# Main.net
KiCad netlist of a schematic drawn in EAGLE
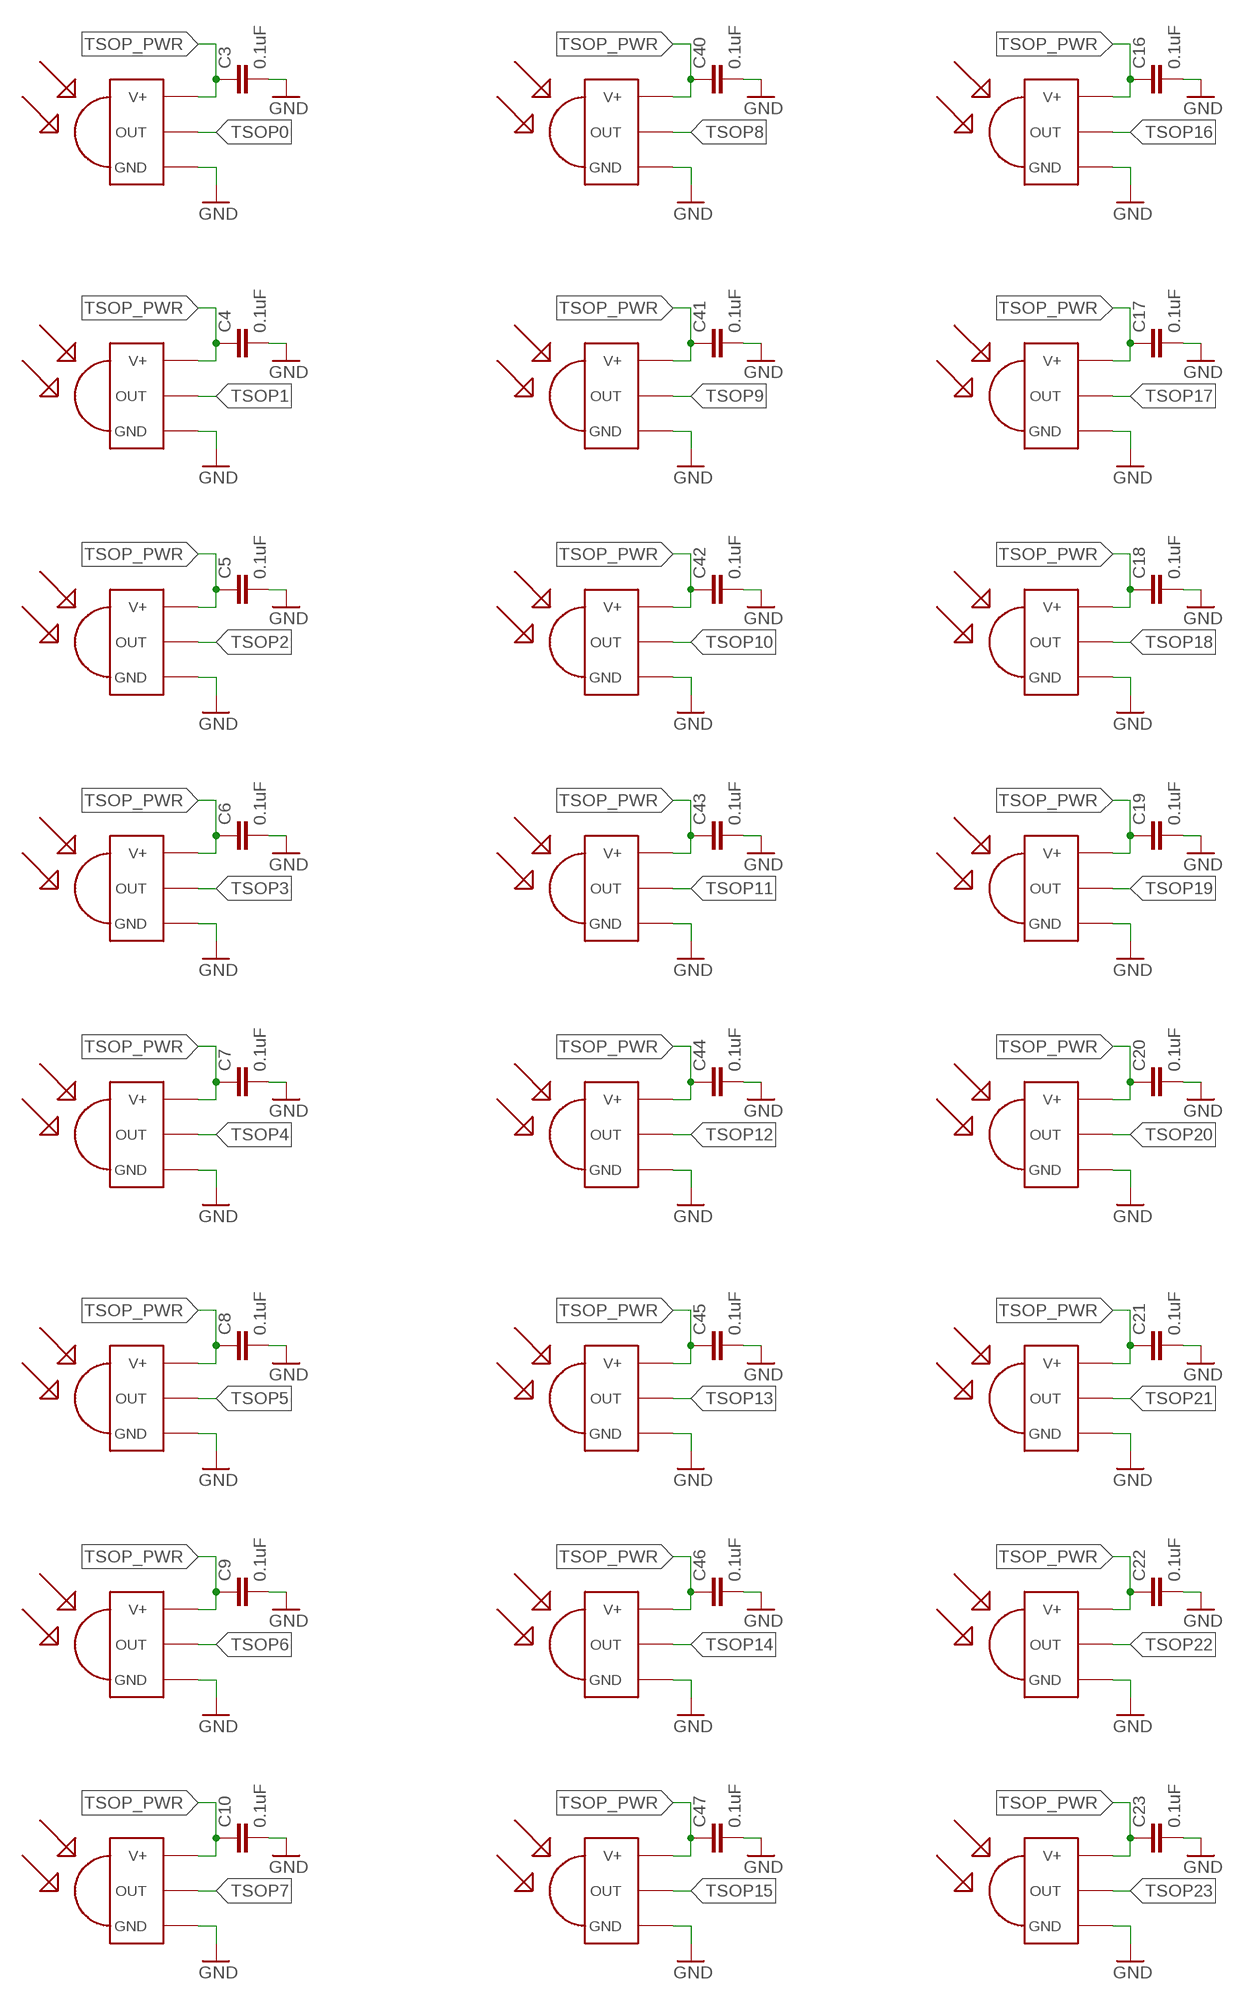
[diagram p0: schematic, sheet 1, part 1 of 3]
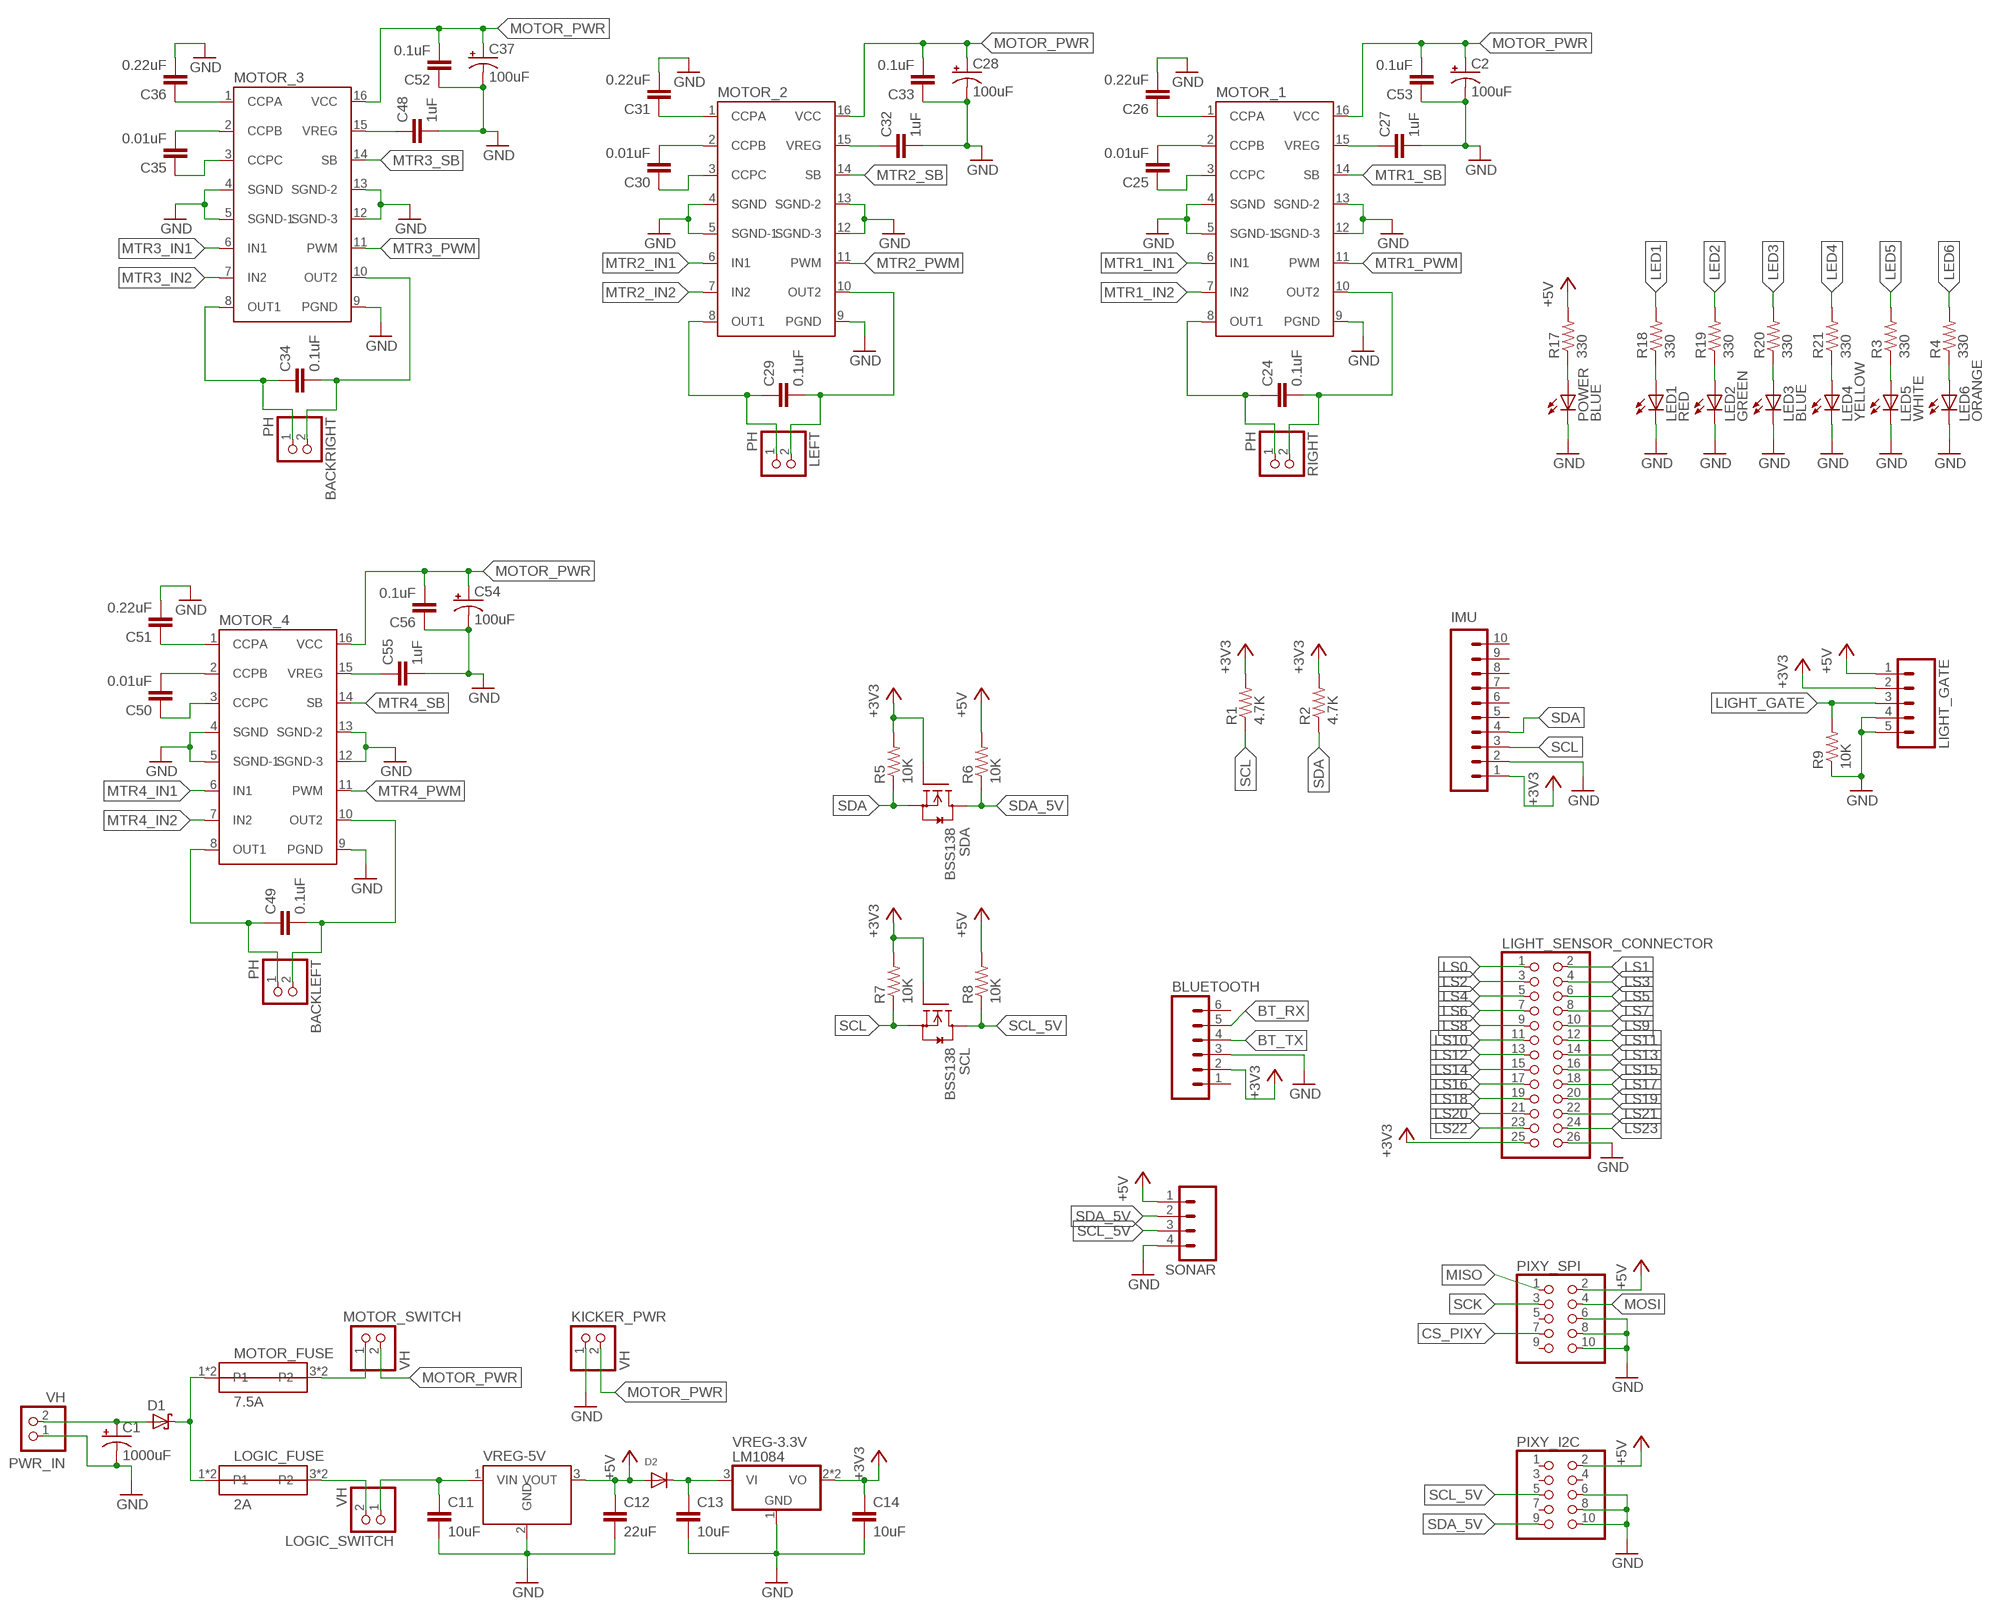
[diagram p1: schematic, sheet 1, part 2 of 3]
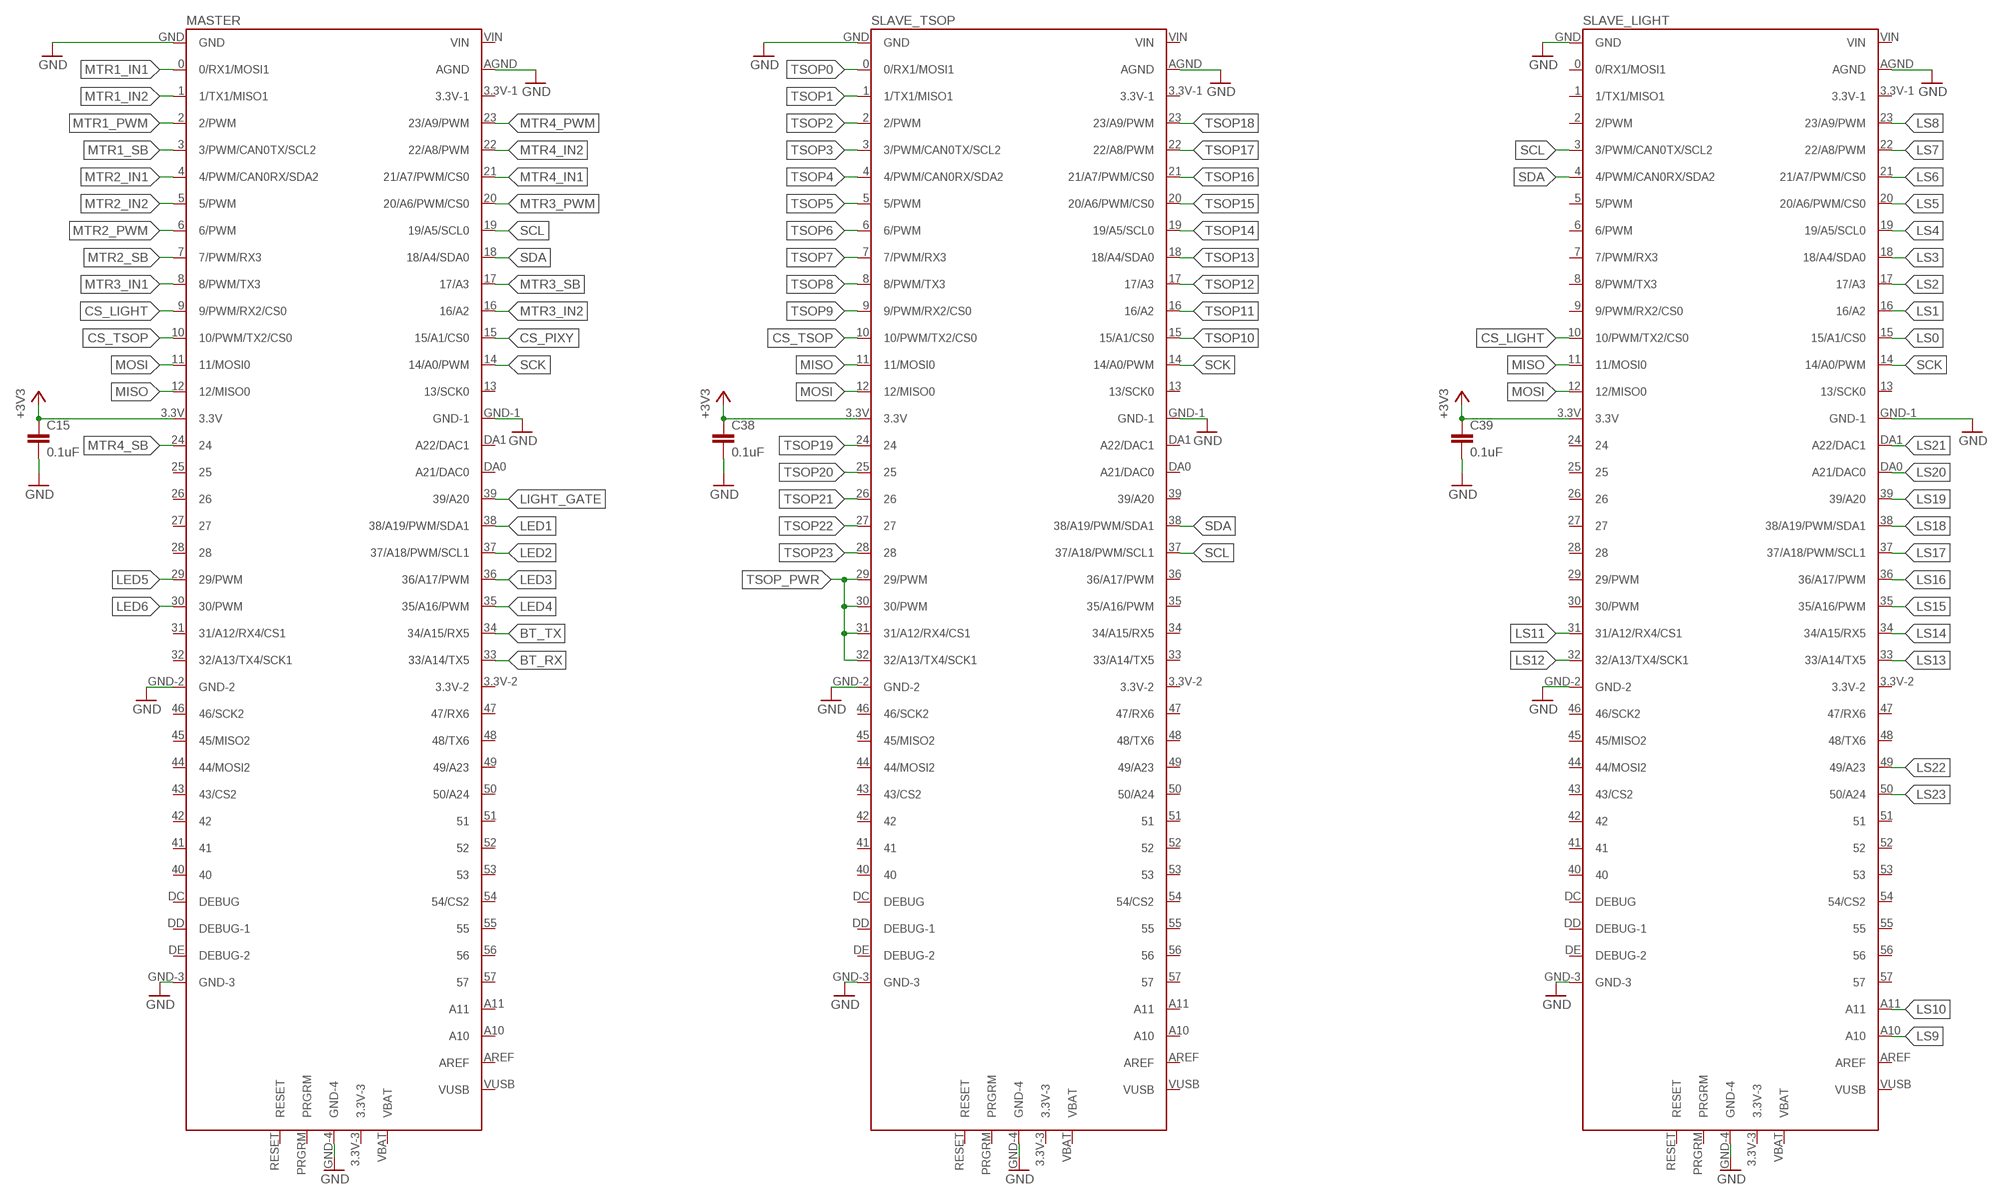
[diagram p2: schematic, sheet 1, part 3 of 3]

(export (version "E")
  (design (tool "Eeschema 10.0.6"))
  (components
    (comp (ref "0")
      (value "TSOP1737")
      (footprint "eagle-import:TSOP17XX")
      (libsource (lib "eagle-import") (part "TSOP1737"))
    )
    (comp (ref "1")
      (value "TSOP1737")
      (footprint "eagle-import:TSOP17XX")
      (libsource (lib "eagle-import") (part "TSOP1737"))
    )
    (comp (ref "2")
      (value "TSOP1737")
      (footprint "eagle-import:TSOP17XX")
      (libsource (lib "eagle-import") (part "TSOP1737"))
    )
    (comp (ref "3")
      (value "TSOP1737")
      (footprint "eagle-import:TSOP17XX")
      (libsource (lib "eagle-import") (part "TSOP1737"))
    )
    (comp (ref "4")
      (value "TSOP1737")
      (footprint "eagle-import:TSOP17XX")
      (libsource (lib "eagle-import") (part "TSOP1737"))
    )
    (comp (ref "5")
      (value "TSOP1737")
      (footprint "eagle-import:TSOP17XX")
      (libsource (lib "eagle-import") (part "TSOP1737"))
    )
    (comp (ref "6")
      (value "TSOP1737")
      (footprint "eagle-import:TSOP17XX")
      (libsource (lib "eagle-import") (part "TSOP1737"))
    )
    (comp (ref "7")
      (value "TSOP1737")
      (footprint "eagle-import:TSOP17XX")
      (libsource (lib "eagle-import") (part "TSOP1737"))
    )
    (comp (ref "8")
      (value "TSOP1737")
      (footprint "eagle-import:TSOP17XX")
      (libsource (lib "eagle-import") (part "TSOP1737"))
    )
    (comp (ref "9")
      (value "TSOP1737")
      (footprint "eagle-import:TSOP17XX")
      (libsource (lib "eagle-import") (part "TSOP1737"))
    )
    (comp (ref "10")
      (value "TSOP1737")
      (footprint "eagle-import:TSOP17XX")
      (libsource (lib "eagle-import") (part "TSOP1737"))
    )
    (comp (ref "11")
      (value "TSOP1737")
      (footprint "eagle-import:TSOP17XX")
      (libsource (lib "eagle-import") (part "TSOP1737"))
    )
    (comp (ref "12")
      (value "TSOP1737")
      (footprint "eagle-import:TSOP17XX")
      (libsource (lib "eagle-import") (part "TSOP1737"))
    )
    (comp (ref "13")
      (value "TSOP1737")
      (footprint "eagle-import:TSOP17XX")
      (libsource (lib "eagle-import") (part "TSOP1737"))
    )
    (comp (ref "14")
      (value "TSOP1737")
      (footprint "eagle-import:TSOP17XX")
      (libsource (lib "eagle-import") (part "TSOP1737"))
    )
    (comp (ref "15")
      (value "TSOP1737")
      (footprint "eagle-import:TSOP17XX")
      (libsource (lib "eagle-import") (part "TSOP1737"))
    )
    (comp (ref "16")
      (value "TSOP1737")
      (footprint "eagle-import:TSOP17XX")
      (libsource (lib "eagle-import") (part "TSOP1737"))
    )
    (comp (ref "17")
      (value "TSOP1737")
      (footprint "eagle-import:TSOP17XX")
      (libsource (lib "eagle-import") (part "TSOP1737"))
    )
    (comp (ref "18")
      (value "TSOP1737")
      (footprint "eagle-import:TSOP17XX")
      (libsource (lib "eagle-import") (part "TSOP1737"))
    )
    (comp (ref "19")
      (value "TSOP1737")
      (footprint "eagle-import:TSOP17XX")
      (libsource (lib "eagle-import") (part "TSOP1737"))
    )
    (comp (ref "20")
      (value "TSOP1737")
      (footprint "eagle-import:TSOP17XX")
      (libsource (lib "eagle-import") (part "TSOP1737"))
    )
    (comp (ref "21")
      (value "TSOP1737")
      (footprint "eagle-import:TSOP17XX")
      (libsource (lib "eagle-import") (part "TSOP1737"))
    )
    (comp (ref "22")
      (value "TSOP1737")
      (footprint "eagle-import:TSOP17XX")
      (libsource (lib "eagle-import") (part "TSOP1737"))
    )
    (comp (ref "23")
      (value "TSOP1737")
      (footprint "eagle-import:TSOP17XX")
      (libsource (lib "eagle-import") (part "TSOP1737"))
    )
    (comp (ref "BACKLEFT")
      (value "PH")
      (footprint "eagle-import:JST-PH-2-THM")
      (libsource (lib "eagle-import") (part "JST_2PIN-THM"))
    )
    (comp (ref "BACKRIGHT")
      (value "PH")
      (footprint "eagle-import:JST-PH-2-THM")
      (libsource (lib "eagle-import") (part "JST_2PIN-THM"))
    )
    (comp (ref "BLUETOOTH")
      (value "M06SILK_FEMALE_PTH")
      (footprint "eagle-import:1X06")
      (libsource (lib "eagle-import") (part "M06SILK_FEMALE_PTH"))
    )
    (comp (ref "C1")
      (value "1000uF")
      (footprint "eagle-import:CPOL-RADIAL-1000UF-25V")
      (libsource (lib "eagle-import") (part "CAP_POLPTH4"))
    )
    (comp (ref "C2")
      (value "100uF")
      (footprint "eagle-import:CPOL-RADIAL-100UF-25V")
      (libsource (lib "eagle-import") (part "CAP_POLPTH1"))
    )
    (comp (ref "C3")
      (value "0.1uF")
      (footprint "eagle-import:0603-CAP")
      (libsource (lib "eagle-import") (part "CAP0603-CAP"))
    )
    (comp (ref "C4")
      (value "0.1uF")
      (footprint "eagle-import:0603-CAP")
      (libsource (lib "eagle-import") (part "CAP0603-CAP"))
    )
    (comp (ref "C5")
      (value "0.1uF")
      (footprint "eagle-import:0603-CAP")
      (libsource (lib "eagle-import") (part "CAP0603-CAP"))
    )
    (comp (ref "C6")
      (value "0.1uF")
      (footprint "eagle-import:0603-CAP")
      (libsource (lib "eagle-import") (part "CAP0603-CAP"))
    )
    (comp (ref "C7")
      (value "0.1uF")
      (footprint "eagle-import:0603-CAP")
      (libsource (lib "eagle-import") (part "CAP0603-CAP"))
    )
    (comp (ref "C8")
      (value "0.1uF")
      (footprint "eagle-import:0603-CAP")
      (libsource (lib "eagle-import") (part "CAP0603-CAP"))
    )
    (comp (ref "C9")
      (value "0.1uF")
      (footprint "eagle-import:0603-CAP")
      (libsource (lib "eagle-import") (part "CAP0603-CAP"))
    )
    (comp (ref "C10")
      (value "0.1uF")
      (footprint "eagle-import:0603-CAP")
      (libsource (lib "eagle-import") (part "CAP0603-CAP"))
    )
    (comp (ref "C11")
      (value "10uF")
      (footprint "eagle-import:0805")
      (libsource (lib "eagle-import") (part "CAP0805"))
    )
    (comp (ref "C12")
      (value "22uF")
      (footprint "eagle-import:0805")
      (libsource (lib "eagle-import") (part "CAP0805"))
    )
    (comp (ref "C13")
      (value "10uF")
      (footprint "eagle-import:0805")
      (libsource (lib "eagle-import") (part "CAP0805"))
    )
    (comp (ref "C14")
      (value "10uF")
      (footprint "eagle-import:0805")
      (libsource (lib "eagle-import") (part "CAP0805"))
    )
    (comp (ref "C15")
      (value "0.1uF")
      (footprint "eagle-import:0603-CAP")
      (libsource (lib "eagle-import") (part "CAP0603-CAP"))
    )
    (comp (ref "C16")
      (value "0.1uF")
      (footprint "eagle-import:0603-CAP")
      (libsource (lib "eagle-import") (part "CAP0603-CAP"))
    )
    (comp (ref "C17")
      (value "0.1uF")
      (footprint "eagle-import:0603-CAP")
      (libsource (lib "eagle-import") (part "CAP0603-CAP"))
    )
    (comp (ref "C18")
      (value "0.1uF")
      (footprint "eagle-import:0603-CAP")
      (libsource (lib "eagle-import") (part "CAP0603-CAP"))
    )
    (comp (ref "C19")
      (value "0.1uF")
      (footprint "eagle-import:0603-CAP")
      (libsource (lib "eagle-import") (part "CAP0603-CAP"))
    )
    (comp (ref "C20")
      (value "0.1uF")
      (footprint "eagle-import:0603-CAP")
      (libsource (lib "eagle-import") (part "CAP0603-CAP"))
    )
    (comp (ref "C21")
      (value "0.1uF")
      (footprint "eagle-import:0603-CAP")
      (libsource (lib "eagle-import") (part "CAP0603-CAP"))
    )
    (comp (ref "C22")
      (value "0.1uF")
      (footprint "eagle-import:0603-CAP")
      (libsource (lib "eagle-import") (part "CAP0603-CAP"))
    )
    (comp (ref "C23")
      (value "0.1uF")
      (footprint "eagle-import:0603-CAP")
      (libsource (lib "eagle-import") (part "CAP0603-CAP"))
    )
    (comp (ref "C24")
      (value "0.1uF")
      (footprint "eagle-import:0603-CAP")
      (libsource (lib "eagle-import") (part "CAP0603-CAP"))
    )
    (comp (ref "C25")
      (value "0.01uF")
      (footprint "eagle-import:0603-CAP")
      (libsource (lib "eagle-import") (part "CAP0603-CAP"))
    )
    (comp (ref "C26")
      (value "0.22uF")
      (footprint "eagle-import:0603-CAP")
      (libsource (lib "eagle-import") (part "CAP0603-CAP"))
    )
    (comp (ref "C27")
      (value "1uF")
      (footprint "eagle-import:0603-CAP")
      (libsource (lib "eagle-import") (part "CAP0603-CAP"))
    )
    (comp (ref "C28")
      (value "100uF")
      (footprint "eagle-import:CPOL-RADIAL-100UF-25V")
      (libsource (lib "eagle-import") (part "CAP_POLPTH1"))
    )
    (comp (ref "C29")
      (value "0.1uF")
      (footprint "eagle-import:0603-CAP")
      (libsource (lib "eagle-import") (part "CAP0603-CAP"))
    )
    (comp (ref "C30")
      (value "0.01uF")
      (footprint "eagle-import:0603-CAP")
      (libsource (lib "eagle-import") (part "CAP0603-CAP"))
    )
    (comp (ref "C31")
      (value "0.22uF")
      (footprint "eagle-import:0603-CAP")
      (libsource (lib "eagle-import") (part "CAP0603-CAP"))
    )
    (comp (ref "C32")
      (value "1uF")
      (footprint "eagle-import:0603-CAP")
      (libsource (lib "eagle-import") (part "CAP0603-CAP"))
    )
    (comp (ref "C33")
      (value "0.1uF")
      (footprint "eagle-import:0603-CAP")
      (libsource (lib "eagle-import") (part "CAP0603-CAP"))
    )
    (comp (ref "C34")
      (value "0.1uF")
      (footprint "eagle-import:0603-CAP")
      (libsource (lib "eagle-import") (part "CAP0603-CAP"))
    )
    (comp (ref "C35")
      (value "0.01uF")
      (footprint "eagle-import:0603-CAP")
      (libsource (lib "eagle-import") (part "CAP0603-CAP"))
    )
    (comp (ref "C36")
      (value "0.22uF")
      (footprint "eagle-import:0603-CAP")
      (libsource (lib "eagle-import") (part "CAP0603-CAP"))
    )
    (comp (ref "C37")
      (value "100uF")
      (footprint "eagle-import:CPOL-RADIAL-100UF-25V")
      (libsource (lib "eagle-import") (part "CAP_POLPTH1"))
    )
    (comp (ref "C38")
      (value "0.1uF")
      (footprint "eagle-import:0603-CAP")
      (libsource (lib "eagle-import") (part "CAP0603-CAP"))
    )
    (comp (ref "C39")
      (value "0.1uF")
      (footprint "eagle-import:0603-CAP")
      (libsource (lib "eagle-import") (part "CAP0603-CAP"))
    )
    (comp (ref "C40")
      (value "0.1uF")
      (footprint "eagle-import:0603-CAP")
      (libsource (lib "eagle-import") (part "CAP0603-CAP"))
    )
    (comp (ref "C41")
      (value "0.1uF")
      (footprint "eagle-import:0603-CAP")
      (libsource (lib "eagle-import") (part "CAP0603-CAP"))
    )
    (comp (ref "C42")
      (value "0.1uF")
      (footprint "eagle-import:0603-CAP")
      (libsource (lib "eagle-import") (part "CAP0603-CAP"))
    )
    (comp (ref "C43")
      (value "0.1uF")
      (footprint "eagle-import:0603-CAP")
      (libsource (lib "eagle-import") (part "CAP0603-CAP"))
    )
    (comp (ref "C44")
      (value "0.1uF")
      (footprint "eagle-import:0603-CAP")
      (libsource (lib "eagle-import") (part "CAP0603-CAP"))
    )
    (comp (ref "C45")
      (value "0.1uF")
      (footprint "eagle-import:0603-CAP")
      (libsource (lib "eagle-import") (part "CAP0603-CAP"))
    )
    (comp (ref "C46")
      (value "0.1uF")
      (footprint "eagle-import:0603-CAP")
      (libsource (lib "eagle-import") (part "CAP0603-CAP"))
    )
    (comp (ref "C47")
      (value "0.1uF")
      (footprint "eagle-import:0603-CAP")
      (libsource (lib "eagle-import") (part "CAP0603-CAP"))
    )
    (comp (ref "C48")
      (value "1uF")
      (footprint "eagle-import:0603-CAP")
      (libsource (lib "eagle-import") (part "CAP0603-CAP"))
    )
    (comp (ref "C49")
      (value "0.1uF")
      (footprint "eagle-import:0603-CAP")
      (libsource (lib "eagle-import") (part "CAP0603-CAP"))
    )
    (comp (ref "C50")
      (value "0.01uF")
      (footprint "eagle-import:0603-CAP")
      (libsource (lib "eagle-import") (part "CAP0603-CAP"))
    )
    (comp (ref "C51")
      (value "0.22uF")
      (footprint "eagle-import:0603-CAP")
      (libsource (lib "eagle-import") (part "CAP0603-CAP"))
    )
    (comp (ref "C52")
      (value "0.1uF")
      (footprint "eagle-import:0603-CAP")
      (libsource (lib "eagle-import") (part "CAP0603-CAP"))
    )
    (comp (ref "C53")
      (value "0.1uF")
      (footprint "eagle-import:0603-CAP")
      (libsource (lib "eagle-import") (part "CAP0603-CAP"))
    )
    (comp (ref "C54")
      (value "100uF")
      (footprint "eagle-import:CPOL-RADIAL-100UF-25V")
      (libsource (lib "eagle-import") (part "CAP_POLPTH1"))
    )
    (comp (ref "C55")
      (value "1uF")
      (footprint "eagle-import:0603-CAP")
      (libsource (lib "eagle-import") (part "CAP0603-CAP"))
    )
    (comp (ref "C56")
      (value "0.1uF")
      (footprint "eagle-import:0603-CAP")
      (libsource (lib "eagle-import") (part "CAP0603-CAP"))
    )
    (comp (ref "D1")
      (value "SCHOTTKY-DIODEP6T15")
      (footprint "eagle-import:P6T15")
      (libsource (lib "eagle-import") (part "SCHOTTKY-DIODEP6T15"))
    )
    (comp (ref "D2")
      (value "DIODE_SOD-123FL")
      (footprint "eagle-import:SOD-123FL")
      (libsource (lib "eagle-import") (part "DIODE_SOD-123FL"))
    )
    (comp (ref "IMU")
      (value "M10SILK_FEMALE_PTH")
      (footprint "eagle-import:1X10")
      (libsource (lib "eagle-import") (part "M10SILK_FEMALE_PTH"))
    )
    (comp (ref "KICKER_PWR")
      (value "VH")
      (footprint "eagle-import:B2P-VH")
      (libsource (lib "eagle-import") (part "B2P-VH"))
    )
    (comp (ref "LED1")
      (value "RED")
      (footprint "eagle-import:CHIPLED_0603")
      (libsource (lib "eagle-import") (part "LEDCHIPLED_0603"))
    )
    (comp (ref "LED2")
      (value "GREEN")
      (footprint "eagle-import:CHIPLED_0603")
      (libsource (lib "eagle-import") (part "LEDCHIPLED_0603"))
    )
    (comp (ref "LED3")
      (value "BLUE")
      (footprint "eagle-import:CHIPLED_0603")
      (libsource (lib "eagle-import") (part "LEDCHIPLED_0603"))
    )
    (comp (ref "LED4")
      (value "YELLOW")
      (footprint "eagle-import:CHIPLED_0603")
      (libsource (lib "eagle-import") (part "LEDCHIPLED_0603"))
    )
    (comp (ref "LED5")
      (value "WHITE")
      (footprint "eagle-import:CHIPLED_0603")
      (libsource (lib "eagle-import") (part "LEDCHIPLED_0603"))
    )
    (comp (ref "LED6")
      (value "ORANGE")
      (footprint "eagle-import:CHIPLED_0603")
      (libsource (lib "eagle-import") (part "LEDCHIPLED_0603"))
    )
    (comp (ref "LEFT")
      (value "PH")
      (footprint "eagle-import:JST-PH-2-THM")
      (libsource (lib "eagle-import") (part "JST_2PIN-THM"))
    )
    (comp (ref "LIGHT_GATE")
      (value "M05PTH")
      (footprint "eagle-import:1X05")
      (libsource (lib "eagle-import") (part "M05PTH"))
    )
    (comp (ref "LIGHT_SENSOR_CONNECTOR")
      (value "PINHD-2X13SMT")
      (footprint "eagle-import:2X13_SMT")
      (libsource (lib "eagle-import") (part "PINHD-2X13SMT"))
    )
    (comp (ref "LOGIC_FUSE")
      (value "2A")
      (footprint "eagle-import:3568-FUSEHOLDER")
      (libsource (lib "eagle-import") (part "3568-FUSEHOLDER"))
    )
    (comp (ref "LOGIC_SWITCH")
      (value "VH")
      (footprint "eagle-import:B2P-VH")
      (libsource (lib "eagle-import") (part "B2P-VH"))
    )
    (comp (ref "MASTER")
      (value "TEENSY-3.5")
      (footprint "eagle-import:TEENSY-3.5")
      (libsource (lib "eagle-import") (part "TEENSY-3.5"))
    )
    (comp (ref "MOTOR_1")
      (value "TB6549PG")
      (footprint "eagle-import:TB6549PG")
      (libsource (lib "eagle-import") (part "TB6549PG"))
    )
    (comp (ref "MOTOR_2")
      (value "TB6549PG")
      (footprint "eagle-import:TB6549PG")
      (libsource (lib "eagle-import") (part "TB6549PG"))
    )
    (comp (ref "MOTOR_3")
      (value "TB6549PG")
      (footprint "eagle-import:TB6549PG")
      (libsource (lib "eagle-import") (part "TB6549PG"))
    )
    (comp (ref "MOTOR_4")
      (value "TB6549PG")
      (footprint "eagle-import:TB6549PG")
      (libsource (lib "eagle-import") (part "TB6549PG"))
    )
    (comp (ref "MOTOR_FUSE")
      (value "7.5A")
      (footprint "eagle-import:3568-FUSEHOLDER")
      (libsource (lib "eagle-import") (part "3568-FUSEHOLDER"))
    )
    (comp (ref "MOTOR_SWITCH")
      (value "VH")
      (footprint "eagle-import:B2P-VH")
      (libsource (lib "eagle-import") (part "B2P-VH"))
    )
    (comp (ref "PIXY_I2C")
      (value "PINHD-2X5SMT")
      (footprint "eagle-import:2X05_SMT")
      (libsource (lib "eagle-import") (part "PINHD-2X5SMT"))
    )
    (comp (ref "PIXY_SPI")
      (value "PINHD-2X5SMT")
      (footprint "eagle-import:2X05_SMT")
      (libsource (lib "eagle-import") (part "PINHD-2X5SMT"))
    )
    (comp (ref "POWER")
      (value "BLUE")
      (footprint "eagle-import:CHIPLED_0603")
      (libsource (lib "eagle-import") (part "LEDCHIPLED_0603"))
    )
    (comp (ref "PWR_IN")
      (value "VH")
      (footprint "eagle-import:B2P-VH")
      (libsource (lib "eagle-import") (part "B2P-VH"))
    )
    (comp (ref "R1")
      (value "4.7K")
      (footprint "eagle-import:0603-RES")
      (libsource (lib "eagle-import") (part "RESISTOR0603"))
    )
    (comp (ref "R2")
      (value "4.7K")
      (footprint "eagle-import:0603-RES")
      (libsource (lib "eagle-import") (part "RESISTOR0603"))
    )
    (comp (ref "R3")
      (value "330")
      (footprint "eagle-import:0603-RES")
      (libsource (lib "eagle-import") (part "RESISTOR0603"))
    )
    (comp (ref "R4")
      (value "330")
      (footprint "eagle-import:0603-RES")
      (libsource (lib "eagle-import") (part "RESISTOR0603"))
    )
    (comp (ref "R5")
      (value "10K")
      (footprint "eagle-import:0603-RES")
      (libsource (lib "eagle-import") (part "RESISTOR0603-RES"))
    )
    (comp (ref "R6")
      (value "10K")
      (footprint "eagle-import:0603-RES")
      (libsource (lib "eagle-import") (part "RESISTOR0603-RES"))
    )
    (comp (ref "R7")
      (value "10K")
      (footprint "eagle-import:0603-RES")
      (libsource (lib "eagle-import") (part "RESISTOR0603-RES"))
    )
    (comp (ref "R8")
      (value "10K")
      (footprint "eagle-import:0603-RES")
      (libsource (lib "eagle-import") (part "RESISTOR0603-RES"))
    )
    (comp (ref "R9")
      (value "10K")
      (footprint "eagle-import:0603-RES")
      (libsource (lib "eagle-import") (part "RESISTOR0603-RES"))
    )
    (comp (ref "R17")
      (value "330")
      (footprint "eagle-import:0603-RES")
      (libsource (lib "eagle-import") (part "RESISTOR0603"))
    )
    (comp (ref "R18")
      (value "330")
      (footprint "eagle-import:0603-RES")
      (libsource (lib "eagle-import") (part "RESISTOR0603"))
    )
    (comp (ref "R19")
      (value "330")
      (footprint "eagle-import:0603-RES")
      (libsource (lib "eagle-import") (part "RESISTOR0603"))
    )
    (comp (ref "R20")
      (value "330")
      (footprint "eagle-import:0603-RES")
      (libsource (lib "eagle-import") (part "RESISTOR0603"))
    )
    (comp (ref "R21")
      (value "330")
      (footprint "eagle-import:0603-RES")
      (libsource (lib "eagle-import") (part "RESISTOR0603"))
    )
    (comp (ref "RIGHT")
      (value "PH")
      (footprint "eagle-import:JST-PH-2-THM")
      (libsource (lib "eagle-import") (part "JST_2PIN-THM"))
    )
    (comp (ref "SCL")
      (value "BSS138")
      (footprint "eagle-import:SOT23")
      (libsource (lib "eagle-import") (part "BSS138"))
    )
    (comp (ref "SDA")
      (value "BSS138")
      (footprint "eagle-import:SOT23")
      (libsource (lib "eagle-import") (part "BSS138"))
    )
    (comp (ref "SLAVE_LIGHT")
      (value "TEENSY-3.5")
      (footprint "eagle-import:TEENSY-3.5")
      (libsource (lib "eagle-import") (part "TEENSY-3.5"))
    )
    (comp (ref "SLAVE_TSOP")
      (value "TEENSY-3.5")
      (footprint "eagle-import:TEENSY-3.5")
      (libsource (lib "eagle-import") (part "TEENSY-3.5"))
    )
    (comp (ref "SONAR")
      (value "M04PTH")
      (footprint "eagle-import:1X04")
      (libsource (lib "eagle-import") (part "M04PTH"))
    )
    (comp (ref "VREG-3.3V")
      (value "LM1084")
      (footprint "eagle-import:TO263-3")
      (libsource (lib "eagle-import") (part "LM340?-S05"))
    )
    (comp (ref "VREG-5V")
      (value "V78-2000")
      (footprint "eagle-import:V78-2000")
      (libsource (lib "eagle-import") (part "V78-2000"))
    )
  )
  (nets
    (net (code "1") (name "+3V3") (class "Default")
      (node (ref "BLUETOOTH") (pin "2") (pinfunction "2_2") (pintype "passive"))
      (node (ref "C14") (pin "1") (pinfunction "1_1") (pintype "passive"))
      (node (ref "C15") (pin "1") (pinfunction "1_1") (pintype "passive"))
      (node (ref "C38") (pin "1") (pinfunction "1_1") (pintype "passive"))
      (node (ref "C39") (pin "1") (pinfunction "1_1") (pintype "passive"))
      (node (ref "IMU") (pin "1") (pinfunction "1_1") (pintype "passive"))
      (node (ref "LIGHT_GATE") (pin "2") (pinfunction "2_2") (pintype "passive"))
      (node (ref "LIGHT_SENSOR_CONNECTOR") (pin "25") (pinfunction "25_25") (pintype "passive"))
      (node (ref "MASTER") (pin "3.3V") (pinfunction "3.3V_3.3V") (pintype "bidirectional"))
      (node (ref "R1") (pin "2") (pinfunction "2_2") (pintype "passive"))
      (node (ref "R2") (pin "2") (pinfunction "2_2") (pintype "passive"))
      (node (ref "R5") (pin "2") (pinfunction "2_2") (pintype "passive"))
      (node (ref "R7") (pin "2") (pinfunction "2_2") (pintype "passive"))
      (node (ref "SCL") (pin "1") (pinfunction "G_1") (pintype "passive"))
      (node (ref "SDA") (pin "1") (pinfunction "G_1") (pintype "passive"))
      (node (ref "SLAVE_LIGHT") (pin "3.3V") (pinfunction "3.3V_3.3V") (pintype "bidirectional"))
      (node (ref "SLAVE_TSOP") (pin "3.3V") (pinfunction "3.3V_3.3V") (pintype "bidirectional"))
      (node (ref "VREG-3.3V") (pin "2") (pinfunction "VO_2") (pintype "passive"))
      (node (ref "VREG-3.3V") (pin "TAB") (pinfunction "VO_TAB") (pintype "passive"))
    )
    (net (code "2") (name "+5V") (class "Default")
      (node (ref "C12") (pin "1") (pinfunction "1_1") (pintype "passive"))
      (node (ref "D2") (pin "A") (pinfunction "A_A") (pintype "passive"))
      (node (ref "LIGHT_GATE") (pin "1") (pinfunction "1_1") (pintype "passive"))
      (node (ref "PIXY_I2C") (pin "2") (pinfunction "2_2") (pintype "passive"))
      (node (ref "PIXY_SPI") (pin "2") (pinfunction "2_2") (pintype "passive"))
      (node (ref "R17") (pin "2") (pinfunction "2_2") (pintype "passive"))
      (node (ref "R6") (pin "2") (pinfunction "2_2") (pintype "passive"))
      (node (ref "R8") (pin "2") (pinfunction "2_2") (pintype "passive"))
      (node (ref "SONAR") (pin "1") (pinfunction "1_1") (pintype "passive"))
      (node (ref "VREG-5V") (pin "3") (pinfunction "VOUT_3") (pintype "bidirectional"))
    )
    (net (code "3") (name "BT_RX") (class "Default")
      (node (ref "BLUETOOTH") (pin "5") (pinfunction "5_5") (pintype "passive"))
      (node (ref "MASTER") (pin "33") (pinfunction "33/A14/TX5_33") (pintype "bidirectional"))
    )
    (net (code "4") (name "BT_TX") (class "Default")
      (node (ref "BLUETOOTH") (pin "4") (pinfunction "4_4") (pintype "passive"))
      (node (ref "MASTER") (pin "34") (pinfunction "34/A15/RX5_34") (pintype "bidirectional"))
    )
    (net (code "5") (name "CS_LIGHT") (class "Default")
      (node (ref "MASTER") (pin "9") (pinfunction "9/PWM/RX2/CS0_9") (pintype "bidirectional"))
      (node (ref "SLAVE_LIGHT") (pin "10") (pinfunction "10/PWM/TX2/CS0_10") (pintype "bidirectional"))
    )
    (net (code "6") (name "CS_PIXY") (class "Default")
      (node (ref "MASTER") (pin "15") (pinfunction "15/A1/CS0_15") (pintype "bidirectional"))
      (node (ref "PIXY_SPI") (pin "7") (pinfunction "7_7") (pintype "passive"))
    )
    (net (code "7") (name "CS_TSOP") (class "Default")
      (node (ref "MASTER") (pin "10") (pinfunction "10/PWM/TX2/CS0_10") (pintype "bidirectional"))
      (node (ref "SLAVE_TSOP") (pin "10") (pinfunction "10/PWM/TX2/CS0_10") (pintype "bidirectional"))
    )
    (net (code "8") (name "GND") (class "Default")
      (node (ref "0") (pin "GND") (pinfunction "GND_GND") (pintype "bidirectional"))
      (node (ref "1") (pin "GND") (pinfunction "GND_GND") (pintype "bidirectional"))
      (node (ref "10") (pin "GND") (pinfunction "GND_GND") (pintype "bidirectional"))
      (node (ref "11") (pin "GND") (pinfunction "GND_GND") (pintype "bidirectional"))
      (node (ref "12") (pin "GND") (pinfunction "GND_GND") (pintype "bidirectional"))
      (node (ref "13") (pin "GND") (pinfunction "GND_GND") (pintype "bidirectional"))
      (node (ref "14") (pin "GND") (pinfunction "GND_GND") (pintype "bidirectional"))
      (node (ref "15") (pin "GND") (pinfunction "GND_GND") (pintype "bidirectional"))
      (node (ref "16") (pin "GND") (pinfunction "GND_GND") (pintype "bidirectional"))
      (node (ref "17") (pin "GND") (pinfunction "GND_GND") (pintype "bidirectional"))
      (node (ref "18") (pin "GND") (pinfunction "GND_GND") (pintype "bidirectional"))
      (node (ref "19") (pin "GND") (pinfunction "GND_GND") (pintype "bidirectional"))
      (node (ref "2") (pin "GND") (pinfunction "GND_GND") (pintype "bidirectional"))
      (node (ref "20") (pin "GND") (pinfunction "GND_GND") (pintype "bidirectional"))
      (node (ref "21") (pin "GND") (pinfunction "GND_GND") (pintype "bidirectional"))
      (node (ref "22") (pin "GND") (pinfunction "GND_GND") (pintype "bidirectional"))
      (node (ref "23") (pin "GND") (pinfunction "GND_GND") (pintype "bidirectional"))
      (node (ref "3") (pin "GND") (pinfunction "GND_GND") (pintype "bidirectional"))
      (node (ref "4") (pin "GND") (pinfunction "GND_GND") (pintype "bidirectional"))
      (node (ref "5") (pin "GND") (pinfunction "GND_GND") (pintype "bidirectional"))
      (node (ref "6") (pin "GND") (pinfunction "GND_GND") (pintype "bidirectional"))
      (node (ref "7") (pin "GND") (pinfunction "GND_GND") (pintype "bidirectional"))
      (node (ref "8") (pin "GND") (pinfunction "GND_GND") (pintype "bidirectional"))
      (node (ref "9") (pin "GND") (pinfunction "GND_GND") (pintype "bidirectional"))
      (node (ref "BLUETOOTH") (pin "3") (pinfunction "3_3") (pintype "passive"))
      (node (ref "C1") (pin "-") (pinfunction "-_-") (pintype "passive"))
      (node (ref "C10") (pin "2") (pinfunction "2_2") (pintype "passive"))
      (node (ref "C11") (pin "2") (pinfunction "2_2") (pintype "passive"))
      (node (ref "C12") (pin "2") (pinfunction "2_2") (pintype "passive"))
      (node (ref "C13") (pin "2") (pinfunction "2_2") (pintype "passive"))
      (node (ref "C14") (pin "2") (pinfunction "2_2") (pintype "passive"))
      (node (ref "C15") (pin "2") (pinfunction "2_2") (pintype "passive"))
      (node (ref "C16") (pin "2") (pinfunction "2_2") (pintype "passive"))
      (node (ref "C17") (pin "2") (pinfunction "2_2") (pintype "passive"))
      (node (ref "C18") (pin "2") (pinfunction "2_2") (pintype "passive"))
      (node (ref "C19") (pin "2") (pinfunction "2_2") (pintype "passive"))
      (node (ref "C2") (pin "2") (pinfunction "-_2") (pintype "passive"))
      (node (ref "C20") (pin "2") (pinfunction "2_2") (pintype "passive"))
      (node (ref "C21") (pin "2") (pinfunction "2_2") (pintype "passive"))
      (node (ref "C22") (pin "2") (pinfunction "2_2") (pintype "passive"))
      (node (ref "C23") (pin "2") (pinfunction "2_2") (pintype "passive"))
      (node (ref "C26") (pin "2") (pinfunction "2_2") (pintype "passive"))
      (node (ref "C27") (pin "2") (pinfunction "2_2") (pintype "passive"))
      (node (ref "C28") (pin "2") (pinfunction "-_2") (pintype "passive"))
      (node (ref "C3") (pin "2") (pinfunction "2_2") (pintype "passive"))
      (node (ref "C31") (pin "2") (pinfunction "2_2") (pintype "passive"))
      (node (ref "C32") (pin "2") (pinfunction "2_2") (pintype "passive"))
      (node (ref "C33") (pin "1") (pinfunction "1_1") (pintype "passive"))
      (node (ref "C36") (pin "2") (pinfunction "2_2") (pintype "passive"))
      (node (ref "C37") (pin "2") (pinfunction "-_2") (pintype "passive"))
      (node (ref "C38") (pin "2") (pinfunction "2_2") (pintype "passive"))
      (node (ref "C39") (pin "2") (pinfunction "2_2") (pintype "passive"))
      (node (ref "C4") (pin "2") (pinfunction "2_2") (pintype "passive"))
      (node (ref "C40") (pin "2") (pinfunction "2_2") (pintype "passive"))
      (node (ref "C41") (pin "2") (pinfunction "2_2") (pintype "passive"))
      (node (ref "C42") (pin "2") (pinfunction "2_2") (pintype "passive"))
      (node (ref "C43") (pin "2") (pinfunction "2_2") (pintype "passive"))
      (node (ref "C44") (pin "2") (pinfunction "2_2") (pintype "passive"))
      (node (ref "C45") (pin "2") (pinfunction "2_2") (pintype "passive"))
      (node (ref "C46") (pin "2") (pinfunction "2_2") (pintype "passive"))
      (node (ref "C47") (pin "2") (pinfunction "2_2") (pintype "passive"))
      (node (ref "C48") (pin "2") (pinfunction "2_2") (pintype "passive"))
      (node (ref "C5") (pin "2") (pinfunction "2_2") (pintype "passive"))
      (node (ref "C51") (pin "2") (pinfunction "2_2") (pintype "passive"))
      (node (ref "C52") (pin "1") (pinfunction "1_1") (pintype "passive"))
      (node (ref "C53") (pin "1") (pinfunction "1_1") (pintype "passive"))
      (node (ref "C54") (pin "2") (pinfunction "-_2") (pintype "passive"))
      (node (ref "C55") (pin "2") (pinfunction "2_2") (pintype "passive"))
      (node (ref "C56") (pin "1") (pinfunction "1_1") (pintype "passive"))
      (node (ref "C6") (pin "2") (pinfunction "2_2") (pintype "passive"))
      (node (ref "C7") (pin "2") (pinfunction "2_2") (pintype "passive"))
      (node (ref "C8") (pin "2") (pinfunction "2_2") (pintype "passive"))
      (node (ref "C9") (pin "2") (pinfunction "2_2") (pintype "passive"))
      (node (ref "IMU") (pin "2") (pinfunction "2_2") (pintype "passive"))
      (node (ref "KICKER_PWR") (pin "1") (pinfunction "1_1") (pintype "passive"))
      (node (ref "LED1") (pin "C") (pinfunction "C_C") (pintype "passive"))
      (node (ref "LED2") (pin "C") (pinfunction "C_C") (pintype "passive"))
      (node (ref "LED3") (pin "C") (pinfunction "C_C") (pintype "passive"))
      (node (ref "LED4") (pin "C") (pinfunction "C_C") (pintype "passive"))
      (node (ref "LED5") (pin "C") (pinfunction "C_C") (pintype "passive"))
      (node (ref "LED6") (pin "C") (pinfunction "C_C") (pintype "passive"))
      (node (ref "LIGHT_GATE") (pin "4") (pinfunction "4_4") (pintype "passive"))
      (node (ref "LIGHT_GATE") (pin "5") (pinfunction "5_5") (pintype "passive"))
      (node (ref "LIGHT_SENSOR_CONNECTOR") (pin "26") (pinfunction "26_26") (pintype "passive"))
      (node (ref "MASTER") (pin "AGND") (pinfunction "AGND_AGND") (pintype "bidirectional"))
      (node (ref "MASTER") (pin "GND") (pinfunction "GND_GND") (pintype "bidirectional"))
      (node (ref "MASTER") (pin "GND-1") (pinfunction "GND-1_GND-1") (pintype "bidirectional"))
      (node (ref "MASTER") (pin "GND-2") (pinfunction "GND-2_GND-2") (pintype "bidirectional"))
      (node (ref "MASTER") (pin "GND-3") (pinfunction "GND-3_GND-3") (pintype "bidirectional"))
      (node (ref "MASTER") (pin "GND-4") (pinfunction "GND-4_GND-4") (pintype "bidirectional"))
      (node (ref "MOTOR_1") (pin "12") (pinfunction "SGND-3_12") (pintype "bidirectional"))
      (node (ref "MOTOR_1") (pin "13") (pinfunction "SGND-2_13") (pintype "bidirectional"))
      (node (ref "MOTOR_1") (pin "4") (pinfunction "SGND_4") (pintype "bidirectional"))
      (node (ref "MOTOR_1") (pin "5") (pinfunction "SGND-1_5") (pintype "bidirectional"))
      (node (ref "MOTOR_1") (pin "9") (pinfunction "PGND_9") (pintype "bidirectional"))
      (node (ref "MOTOR_2") (pin "12") (pinfunction "SGND-3_12") (pintype "bidirectional"))
      (node (ref "MOTOR_2") (pin "13") (pinfunction "SGND-2_13") (pintype "bidirectional"))
      (node (ref "MOTOR_2") (pin "4") (pinfunction "SGND_4") (pintype "bidirectional"))
      (node (ref "MOTOR_2") (pin "5") (pinfunction "SGND-1_5") (pintype "bidirectional"))
      (node (ref "MOTOR_2") (pin "9") (pinfunction "PGND_9") (pintype "bidirectional"))
      (node (ref "MOTOR_3") (pin "12") (pinfunction "SGND-3_12") (pintype "bidirectional"))
      (node (ref "MOTOR_3") (pin "13") (pinfunction "SGND-2_13") (pintype "bidirectional"))
      (node (ref "MOTOR_3") (pin "4") (pinfunction "SGND_4") (pintype "bidirectional"))
      (node (ref "MOTOR_3") (pin "5") (pinfunction "SGND-1_5") (pintype "bidirectional"))
      (node (ref "MOTOR_3") (pin "9") (pinfunction "PGND_9") (pintype "bidirectional"))
      (node (ref "MOTOR_4") (pin "12") (pinfunction "SGND-3_12") (pintype "bidirectional"))
      (node (ref "MOTOR_4") (pin "13") (pinfunction "SGND-2_13") (pintype "bidirectional"))
      (node (ref "MOTOR_4") (pin "4") (pinfunction "SGND_4") (pintype "bidirectional"))
      (node (ref "MOTOR_4") (pin "5") (pinfunction "SGND-1_5") (pintype "bidirectional"))
      (node (ref "MOTOR_4") (pin "9") (pinfunction "PGND_9") (pintype "bidirectional"))
      (node (ref "PIXY_I2C") (pin "10") (pinfunction "10_10") (pintype "passive"))
      (node (ref "PIXY_I2C") (pin "6") (pinfunction "6_6") (pintype "passive"))
      (node (ref "PIXY_I2C") (pin "8") (pinfunction "8_8") (pintype "passive"))
      (node (ref "PIXY_SPI") (pin "10") (pinfunction "10_10") (pintype "passive"))
      (node (ref "PIXY_SPI") (pin "6") (pinfunction "6_6") (pintype "passive"))
      (node (ref "PIXY_SPI") (pin "8") (pinfunction "8_8") (pintype "passive"))
      (node (ref "POWER") (pin "C") (pinfunction "C_C") (pintype "passive"))
      (node (ref "PWR_IN") (pin "1") (pinfunction "1_1") (pintype "passive"))
      (node (ref "R9") (pin "1") (pinfunction "1_1") (pintype "passive"))
      (node (ref "SLAVE_LIGHT") (pin "AGND") (pinfunction "AGND_AGND") (pintype "bidirectional"))
      (node (ref "SLAVE_LIGHT") (pin "GND") (pinfunction "GND_GND") (pintype "bidirectional"))
      (node (ref "SLAVE_LIGHT") (pin "GND-1") (pinfunction "GND-1_GND-1") (pintype "bidirectional"))
      (node (ref "SLAVE_LIGHT") (pin "GND-2") (pinfunction "GND-2_GND-2") (pintype "bidirectional"))
      (node (ref "SLAVE_LIGHT") (pin "GND-3") (pinfunction "GND-3_GND-3") (pintype "bidirectional"))
      (node (ref "SLAVE_LIGHT") (pin "GND-4") (pinfunction "GND-4_GND-4") (pintype "bidirectional"))
      (node (ref "SLAVE_TSOP") (pin "AGND") (pinfunction "AGND_AGND") (pintype "bidirectional"))
      (node (ref "SLAVE_TSOP") (pin "GND") (pinfunction "GND_GND") (pintype "bidirectional"))
      (node (ref "SLAVE_TSOP") (pin "GND-1") (pinfunction "GND-1_GND-1") (pintype "bidirectional"))
      (node (ref "SLAVE_TSOP") (pin "GND-2") (pinfunction "GND-2_GND-2") (pintype "bidirectional"))
      (node (ref "SLAVE_TSOP") (pin "GND-3") (pinfunction "GND-3_GND-3") (pintype "bidirectional"))
      (node (ref "SLAVE_TSOP") (pin "GND-4") (pinfunction "GND-4_GND-4") (pintype "bidirectional"))
      (node (ref "SONAR") (pin "4") (pinfunction "4_4") (pintype "passive"))
      (node (ref "VREG-3.3V") (pin "1") (pinfunction "GND_1") (pintype "passive"))
      (node (ref "VREG-5V") (pin "2") (pinfunction "GND_2") (pintype "bidirectional"))
    )
    (net (code "9") (name "LED1") (class "Default")
      (node (ref "MASTER") (pin "38") (pinfunction "38/A19/PWM/SDA1_38") (pintype "bidirectional"))
      (node (ref "R18") (pin "2") (pinfunction "2_2") (pintype "passive"))
    )
    (net (code "10") (name "LED2") (class "Default")
      (node (ref "MASTER") (pin "37") (pinfunction "37/A18/PWM/SCL1_37") (pintype "bidirectional"))
      (node (ref "R19") (pin "2") (pinfunction "2_2") (pintype "passive"))
    )
    (net (code "11") (name "LED3") (class "Default")
      (node (ref "MASTER") (pin "36") (pinfunction "36/A17/PWM_36") (pintype "bidirectional"))
      (node (ref "R20") (pin "2") (pinfunction "2_2") (pintype "passive"))
    )
    (net (code "12") (name "LED4") (class "Default")
      (node (ref "MASTER") (pin "35") (pinfunction "35/A16/PWM_35") (pintype "bidirectional"))
      (node (ref "R21") (pin "2") (pinfunction "2_2") (pintype "passive"))
    )
    (net (code "13") (name "LED5") (class "Default")
      (node (ref "MASTER") (pin "29") (pinfunction "29/PWM_29") (pintype "bidirectional"))
      (node (ref "R3") (pin "2") (pinfunction "2_2") (pintype "passive"))
    )
    (net (code "14") (name "LED6") (class "Default")
      (node (ref "MASTER") (pin "30") (pinfunction "30/PWM_30") (pintype "bidirectional"))
      (node (ref "R4") (pin "2") (pinfunction "2_2") (pintype "passive"))
    )
    (net (code "15") (name "LIGHT_GATE") (class "Default")
      (node (ref "LIGHT_GATE") (pin "3") (pinfunction "3_3") (pintype "passive"))
      (node (ref "MASTER") (pin "39") (pinfunction "39/A20_39") (pintype "bidirectional"))
      (node (ref "R9") (pin "2") (pinfunction "2_2") (pintype "passive"))
    )
    (net (code "16") (name "LS0") (class "Default")
      (node (ref "LIGHT_SENSOR_CONNECTOR") (pin "1") (pinfunction "1_1") (pintype "passive"))
      (node (ref "SLAVE_LIGHT") (pin "15") (pinfunction "15/A1/CS0_15") (pintype "bidirectional"))
    )
    (net (code "17") (name "LS1") (class "Default")
      (node (ref "LIGHT_SENSOR_CONNECTOR") (pin "2") (pinfunction "2_2") (pintype "passive"))
      (node (ref "SLAVE_LIGHT") (pin "16") (pinfunction "16/A2_16") (pintype "bidirectional"))
    )
    (net (code "18") (name "LS2") (class "Default")
      (node (ref "LIGHT_SENSOR_CONNECTOR") (pin "3") (pinfunction "3_3") (pintype "passive"))
      (node (ref "SLAVE_LIGHT") (pin "17") (pinfunction "17/A3_17") (pintype "bidirectional"))
    )
    (net (code "19") (name "LS3") (class "Default")
      (node (ref "LIGHT_SENSOR_CONNECTOR") (pin "4") (pinfunction "4_4") (pintype "passive"))
      (node (ref "SLAVE_LIGHT") (pin "18") (pinfunction "18/A4/SDA0_18") (pintype "bidirectional"))
    )
    (net (code "20") (name "LS4") (class "Default")
      (node (ref "LIGHT_SENSOR_CONNECTOR") (pin "5") (pinfunction "5_5") (pintype "passive"))
      (node (ref "SLAVE_LIGHT") (pin "19") (pinfunction "19/A5/SCL0_19") (pintype "bidirectional"))
    )
    (net (code "21") (name "LS5") (class "Default")
      (node (ref "LIGHT_SENSOR_CONNECTOR") (pin "6") (pinfunction "6_6") (pintype "passive"))
      (node (ref "SLAVE_LIGHT") (pin "20") (pinfunction "20/A6/PWM/CS0_20") (pintype "bidirectional"))
    )
    (net (code "22") (name "LS6") (class "Default")
      (node (ref "LIGHT_SENSOR_CONNECTOR") (pin "7") (pinfunction "7_7") (pintype "passive"))
      (node (ref "SLAVE_LIGHT") (pin "21") (pinfunction "21/A7/PWM/CS0_21") (pintype "bidirectional"))
    )
    (net (code "23") (name "LS7") (class "Default")
      (node (ref "LIGHT_SENSOR_CONNECTOR") (pin "8") (pinfunction "8_8") (pintype "passive"))
      (node (ref "SLAVE_LIGHT") (pin "22") (pinfunction "22/A8/PWM_22") (pintype "bidirectional"))
    )
    (net (code "24") (name "LS8") (class "Default")
      (node (ref "LIGHT_SENSOR_CONNECTOR") (pin "9") (pinfunction "9_9") (pintype "passive"))
      (node (ref "SLAVE_LIGHT") (pin "23") (pinfunction "23/A9/PWM_23") (pintype "bidirectional"))
    )
    (net (code "25") (name "LS9") (class "Default")
      (node (ref "LIGHT_SENSOR_CONNECTOR") (pin "10") (pinfunction "10_10") (pintype "passive"))
      (node (ref "SLAVE_LIGHT") (pin "A10") (pinfunction "A10_A10") (pintype "bidirectional"))
    )
    (net (code "26") (name "LS10") (class "Default")
      (node (ref "LIGHT_SENSOR_CONNECTOR") (pin "11") (pinfunction "11_11") (pintype "passive"))
      (node (ref "SLAVE_LIGHT") (pin "A11") (pinfunction "A11_A11") (pintype "bidirectional"))
    )
    (net (code "27") (name "LS11") (class "Default")
      (node (ref "LIGHT_SENSOR_CONNECTOR") (pin "12") (pinfunction "12_12") (pintype "passive"))
      (node (ref "SLAVE_LIGHT") (pin "31") (pinfunction "31/A12/RX4/CS1_31") (pintype "bidirectional"))
    )
    (net (code "28") (name "LS12") (class "Default")
      (node (ref "LIGHT_SENSOR_CONNECTOR") (pin "13") (pinfunction "13_13") (pintype "passive"))
      (node (ref "SLAVE_LIGHT") (pin "32") (pinfunction "32/A13/TX4/SCK1_32") (pintype "bidirectional"))
    )
    (net (code "29") (name "LS13") (class "Default")
      (node (ref "LIGHT_SENSOR_CONNECTOR") (pin "14") (pinfunction "14_14") (pintype "passive"))
      (node (ref "SLAVE_LIGHT") (pin "33") (pinfunction "33/A14/TX5_33") (pintype "bidirectional"))
    )
    (net (code "30") (name "LS14") (class "Default")
      (node (ref "LIGHT_SENSOR_CONNECTOR") (pin "15") (pinfunction "15_15") (pintype "passive"))
      (node (ref "SLAVE_LIGHT") (pin "34") (pinfunction "34/A15/RX5_34") (pintype "bidirectional"))
    )
    (net (code "31") (name "LS15") (class "Default")
      (node (ref "LIGHT_SENSOR_CONNECTOR") (pin "16") (pinfunction "16_16") (pintype "passive"))
      (node (ref "SLAVE_LIGHT") (pin "35") (pinfunction "35/A16/PWM_35") (pintype "bidirectional"))
    )
    (net (code "32") (name "LS16") (class "Default")
      (node (ref "LIGHT_SENSOR_CONNECTOR") (pin "17") (pinfunction "17_17") (pintype "passive"))
      (node (ref "SLAVE_LIGHT") (pin "36") (pinfunction "36/A17/PWM_36") (pintype "bidirectional"))
    )
    (net (code "33") (name "LS17") (class "Default")
      (node (ref "LIGHT_SENSOR_CONNECTOR") (pin "18") (pinfunction "18_18") (pintype "passive"))
      (node (ref "SLAVE_LIGHT") (pin "37") (pinfunction "37/A18/PWM/SCL1_37") (pintype "bidirectional"))
    )
    (net (code "34") (name "LS18") (class "Default")
      (node (ref "LIGHT_SENSOR_CONNECTOR") (pin "19") (pinfunction "19_19") (pintype "passive"))
      (node (ref "SLAVE_LIGHT") (pin "38") (pinfunction "38/A19/PWM/SDA1_38") (pintype "bidirectional"))
    )
    (net (code "35") (name "LS19") (class "Default")
      (node (ref "LIGHT_SENSOR_CONNECTOR") (pin "20") (pinfunction "20_20") (pintype "passive"))
      (node (ref "SLAVE_LIGHT") (pin "39") (pinfunction "39/A20_39") (pintype "bidirectional"))
    )
    (net (code "36") (name "LS20") (class "Default")
      (node (ref "LIGHT_SENSOR_CONNECTOR") (pin "21") (pinfunction "21_21") (pintype "passive"))
      (node (ref "SLAVE_LIGHT") (pin "DA0") (pinfunction "A21/DAC0_DA0") (pintype "bidirectional"))
    )
    (net (code "37") (name "LS21") (class "Default")
      (node (ref "LIGHT_SENSOR_CONNECTOR") (pin "22") (pinfunction "22_22") (pintype "passive"))
      (node (ref "SLAVE_LIGHT") (pin "DA1") (pinfunction "A22/DAC1_DA1") (pintype "bidirectional"))
    )
    (net (code "38") (name "LS22") (class "Default")
      (node (ref "LIGHT_SENSOR_CONNECTOR") (pin "23") (pinfunction "23_23") (pintype "passive"))
      (node (ref "SLAVE_LIGHT") (pin "49") (pinfunction "49/A23_49") (pintype "bidirectional"))
    )
    (net (code "39") (name "LS23") (class "Default")
      (node (ref "LIGHT_SENSOR_CONNECTOR") (pin "24") (pinfunction "24_24") (pintype "passive"))
      (node (ref "SLAVE_LIGHT") (pin "50") (pinfunction "50/A24_50") (pintype "bidirectional"))
    )
    (net (code "40") (name "MISO") (class "Default")
      (node (ref "MASTER") (pin "12") (pinfunction "12/MISO0_12") (pintype "bidirectional"))
      (node (ref "PIXY_SPI") (pin "1") (pinfunction "1_1") (pintype "passive"))
      (node (ref "SLAVE_LIGHT") (pin "11") (pinfunction "11/MOSI0_11") (pintype "bidirectional"))
      (node (ref "SLAVE_TSOP") (pin "11") (pinfunction "11/MOSI0_11") (pintype "bidirectional"))
    )
    (net (code "41") (name "MOSI") (class "Default")
      (node (ref "MASTER") (pin "11") (pinfunction "11/MOSI0_11") (pintype "bidirectional"))
      (node (ref "PIXY_SPI") (pin "4") (pinfunction "4_4") (pintype "passive"))
      (node (ref "SLAVE_LIGHT") (pin "12") (pinfunction "12/MISO0_12") (pintype "bidirectional"))
      (node (ref "SLAVE_TSOP") (pin "12") (pinfunction "12/MISO0_12") (pintype "bidirectional"))
    )
    (net (code "42") (name "MOTOR_PWR") (class "Default")
      (node (ref "C2") (pin "1") (pinfunction "+_1") (pintype "passive"))
      (node (ref "C28") (pin "1") (pinfunction "+_1") (pintype "passive"))
      (node (ref "C33") (pin "2") (pinfunction "2_2") (pintype "passive"))
      (node (ref "C37") (pin "1") (pinfunction "+_1") (pintype "passive"))
      (node (ref "C52") (pin "2") (pinfunction "2_2") (pintype "passive"))
      (node (ref "C53") (pin "2") (pinfunction "2_2") (pintype "passive"))
      (node (ref "C54") (pin "1") (pinfunction "+_1") (pintype "passive"))
      (node (ref "C56") (pin "2") (pinfunction "2_2") (pintype "passive"))
      (node (ref "KICKER_PWR") (pin "2") (pinfunction "2_2") (pintype "passive"))
      (node (ref "MOTOR_1") (pin "16") (pinfunction "VCC_16") (pintype "bidirectional"))
      (node (ref "MOTOR_2") (pin "16") (pinfunction "VCC_16") (pintype "bidirectional"))
      (node (ref "MOTOR_3") (pin "16") (pinfunction "VCC_16") (pintype "bidirectional"))
      (node (ref "MOTOR_4") (pin "16") (pinfunction "VCC_16") (pintype "bidirectional"))
      (node (ref "MOTOR_SWITCH") (pin "2") (pinfunction "2_2") (pintype "passive"))
    )
    (net (code "43") (name "MTR1_IN1") (class "Default")
      (node (ref "MASTER") (pin "0") (pinfunction "0/RX1/MOSI1_0") (pintype "bidirectional"))
      (node (ref "MOTOR_1") (pin "6") (pinfunction "IN1_6") (pintype "bidirectional"))
    )
    (net (code "44") (name "MTR1_IN2") (class "Default")
      (node (ref "MASTER") (pin "1") (pinfunction "1/TX1/MISO1_1") (pintype "bidirectional"))
      (node (ref "MOTOR_1") (pin "7") (pinfunction "IN2_7") (pintype "bidirectional"))
    )
    (net (code "45") (name "MTR1_PWM") (class "Default")
      (node (ref "MASTER") (pin "2") (pinfunction "2/PWM_2") (pintype "bidirectional"))
      (node (ref "MOTOR_1") (pin "11") (pinfunction "PWM_11") (pintype "bidirectional"))
    )
    (net (code "46") (name "MTR1_SB") (class "Default")
      (node (ref "MASTER") (pin "3") (pinfunction "3/PWM/CAN0TX/SCL2_3") (pintype "bidirectional"))
      (node (ref "MOTOR_1") (pin "14") (pinfunction "SB_14") (pintype "bidirectional"))
    )
    (net (code "47") (name "MTR2_IN1") (class "Default")
      (node (ref "MASTER") (pin "4") (pinfunction "4/PWM/CAN0RX/SDA2_4") (pintype "bidirectional"))
      (node (ref "MOTOR_2") (pin "6") (pinfunction "IN1_6") (pintype "bidirectional"))
    )
    (net (code "48") (name "MTR2_IN2") (class "Default")
      (node (ref "MASTER") (pin "5") (pinfunction "5/PWM_5") (pintype "bidirectional"))
      (node (ref "MOTOR_2") (pin "7") (pinfunction "IN2_7") (pintype "bidirectional"))
    )
    (net (code "49") (name "MTR2_PWM") (class "Default")
      (node (ref "MASTER") (pin "6") (pinfunction "6/PWM_6") (pintype "bidirectional"))
      (node (ref "MOTOR_2") (pin "11") (pinfunction "PWM_11") (pintype "bidirectional"))
    )
    (net (code "50") (name "MTR2_SB") (class "Default")
      (node (ref "MASTER") (pin "7") (pinfunction "7/PWM/RX3_7") (pintype "bidirectional"))
      (node (ref "MOTOR_2") (pin "14") (pinfunction "SB_14") (pintype "bidirectional"))
    )
    (net (code "51") (name "MTR3_IN1") (class "Default")
      (node (ref "MASTER") (pin "8") (pinfunction "8/PWM/TX3_8") (pintype "bidirectional"))
      (node (ref "MOTOR_3") (pin "6") (pinfunction "IN1_6") (pintype "bidirectional"))
    )
    (net (code "52") (name "MTR3_IN2") (class "Default")
      (node (ref "MASTER") (pin "16") (pinfunction "16/A2_16") (pintype "bidirectional"))
      (node (ref "MOTOR_3") (pin "7") (pinfunction "IN2_7") (pintype "bidirectional"))
    )
    (net (code "53") (name "MTR3_PWM") (class "Default")
      (node (ref "MASTER") (pin "20") (pinfunction "20/A6/PWM/CS0_20") (pintype "bidirectional"))
      (node (ref "MOTOR_3") (pin "11") (pinfunction "PWM_11") (pintype "bidirectional"))
    )
    (net (code "54") (name "MTR3_SB") (class "Default")
      (node (ref "MASTER") (pin "17") (pinfunction "17/A3_17") (pintype "bidirectional"))
      (node (ref "MOTOR_3") (pin "14") (pinfunction "SB_14") (pintype "bidirectional"))
    )
    (net (code "55") (name "MTR4_IN1") (class "Default")
      (node (ref "MASTER") (pin "21") (pinfunction "21/A7/PWM/CS0_21") (pintype "bidirectional"))
      (node (ref "MOTOR_4") (pin "6") (pinfunction "IN1_6") (pintype "bidirectional"))
    )
    (net (code "56") (name "MTR4_IN2") (class "Default")
      (node (ref "MASTER") (pin "22") (pinfunction "22/A8/PWM_22") (pintype "bidirectional"))
      (node (ref "MOTOR_4") (pin "7") (pinfunction "IN2_7") (pintype "bidirectional"))
    )
    (net (code "57") (name "MTR4_PWM") (class "Default")
      (node (ref "MASTER") (pin "23") (pinfunction "23/A9/PWM_23") (pintype "bidirectional"))
      (node (ref "MOTOR_4") (pin "11") (pinfunction "PWM_11") (pintype "bidirectional"))
    )
    (net (code "58") (name "MTR4_SB") (class "Default")
      (node (ref "MASTER") (pin "24") (pinfunction "24_24") (pintype "bidirectional"))
      (node (ref "MOTOR_4") (pin "14") (pinfunction "SB_14") (pintype "bidirectional"))
    )
    (net (code "59") (name "Net-(BACKLEFT-1)") (class "Default")
      (node (ref "BACKLEFT") (pin "2") (pinfunction "1_2") (pintype "passive"))
      (node (ref "C49") (pin "2") (pinfunction "2_2") (pintype "passive"))
      (node (ref "MOTOR_4") (pin "10") (pinfunction "OUT2_10") (pintype "bidirectional"))
    )
    (net (code "60") (name "Net-(BACKLEFT-2)") (class "Default")
      (node (ref "BACKLEFT") (pin "1") (pinfunction "2_1") (pintype "passive"))
      (node (ref "C49") (pin "1") (pinfunction "1_1") (pintype "passive"))
      (node (ref "MOTOR_4") (pin "8") (pinfunction "OUT1_8") (pintype "bidirectional"))
    )
    (net (code "61") (name "Net-(BACKRIGHT-1)") (class "Default")
      (node (ref "BACKRIGHT") (pin "2") (pinfunction "1_2") (pintype "passive"))
      (node (ref "C34") (pin "2") (pinfunction "2_2") (pintype "passive"))
      (node (ref "MOTOR_3") (pin "10") (pinfunction "OUT2_10") (pintype "bidirectional"))
    )
    (net (code "62") (name "Net-(BACKRIGHT-2)") (class "Default")
      (node (ref "BACKRIGHT") (pin "1") (pinfunction "2_1") (pintype "passive"))
      (node (ref "C34") (pin "1") (pinfunction "1_1") (pintype "passive"))
      (node (ref "MOTOR_3") (pin "8") (pinfunction "OUT1_8") (pintype "bidirectional"))
    )
    (net (code "63") (name "Net-(C1-Pad+)") (class "Default")
      (node (ref "C1") (pin "+") (pinfunction "+_+") (pintype "passive"))
      (node (ref "D1") (pin "A") (pinfunction "A_A") (pintype "passive"))
      (node (ref "PWR_IN") (pin "2") (pinfunction "2_2") (pintype "passive"))
    )
    (net (code "64") (name "Net-(D1-PadC)") (class "Default")
      (node (ref "D1") (pin "C") (pinfunction "C_C") (pintype "passive"))
      (node (ref "LOGIC_FUSE") (pin "1") (pinfunction "P1_1") (pintype "bidirectional"))
      (node (ref "LOGIC_FUSE") (pin "2") (pinfunction "P1_2") (pintype "bidirectional"))
      (node (ref "MOTOR_FUSE") (pin "1") (pinfunction "P1_1") (pintype "bidirectional"))
      (node (ref "MOTOR_FUSE") (pin "2") (pinfunction "P1_2") (pintype "bidirectional"))
    )
    (net (code "65") (name "Net-(LED1-PadA)") (class "Default")
      (node (ref "LED1") (pin "A") (pinfunction "A_A") (pintype "passive"))
      (node (ref "R18") (pin "1") (pinfunction "1_1") (pintype "passive"))
    )
    (net (code "66") (name "Net-(LED2-PadA)") (class "Default")
      (node (ref "LED2") (pin "A") (pinfunction "A_A") (pintype "passive"))
      (node (ref "R19") (pin "1") (pinfunction "1_1") (pintype "passive"))
    )
    (net (code "67") (name "Net-(LED3-PadA)") (class "Default")
      (node (ref "LED3") (pin "A") (pinfunction "A_A") (pintype "passive"))
      (node (ref "R20") (pin "1") (pinfunction "1_1") (pintype "passive"))
    )
    (net (code "68") (name "Net-(LED4-PadA)") (class "Default")
      (node (ref "LED4") (pin "A") (pinfunction "A_A") (pintype "passive"))
      (node (ref "R21") (pin "1") (pinfunction "1_1") (pintype "passive"))
    )
    (net (code "69") (name "Net-(LED5-PadA)") (class "Default")
      (node (ref "LED5") (pin "A") (pinfunction "A_A") (pintype "passive"))
      (node (ref "R3") (pin "1") (pinfunction "1_1") (pintype "passive"))
    )
    (net (code "70") (name "Net-(LED6-PadA)") (class "Default")
      (node (ref "LED6") (pin "A") (pinfunction "A_A") (pintype "passive"))
      (node (ref "R4") (pin "1") (pinfunction "1_1") (pintype "passive"))
    )
    (net (code "71") (name "Net-(LEFT-1)") (class "Default")
      (node (ref "C29") (pin "2") (pinfunction "2_2") (pintype "passive"))
      (node (ref "LEFT") (pin "2") (pinfunction "1_2") (pintype "passive"))
      (node (ref "MOTOR_2") (pin "10") (pinfunction "OUT2_10") (pintype "bidirectional"))
    )
    (net (code "72") (name "Net-(LEFT-2)") (class "Default")
      (node (ref "C29") (pin "1") (pinfunction "1_1") (pintype "passive"))
      (node (ref "LEFT") (pin "1") (pinfunction "2_1") (pintype "passive"))
      (node (ref "MOTOR_2") (pin "8") (pinfunction "OUT1_8") (pintype "bidirectional"))
    )
    (net (code "73") (name "Net-(LOGIC_FUSE-P2-Pad3)") (class "Default")
      (node (ref "LOGIC_FUSE") (pin "3") (pinfunction "P2_3") (pintype "bidirectional"))
      (node (ref "LOGIC_FUSE") (pin "4") (pinfunction "P2_4") (pintype "bidirectional"))
      (node (ref "LOGIC_SWITCH") (pin "2") (pinfunction "2_2") (pintype "passive"))
    )
    (net (code "74") (name "Net-(MOTOR_1-CCPA)") (class "Default")
      (node (ref "C26") (pin "1") (pinfunction "1_1") (pintype "passive"))
      (node (ref "MOTOR_1") (pin "1") (pinfunction "CCPA_1") (pintype "bidirectional"))
    )
    (net (code "75") (name "Net-(MOTOR_1-CCPB)") (class "Default")
      (node (ref "C25") (pin "2") (pinfunction "2_2") (pintype "passive"))
      (node (ref "MOTOR_1") (pin "2") (pinfunction "CCPB_2") (pintype "bidirectional"))
    )
    (net (code "76") (name "Net-(MOTOR_1-CCPC)") (class "Default")
      (node (ref "C25") (pin "1") (pinfunction "1_1") (pintype "passive"))
      (node (ref "MOTOR_1") (pin "3") (pinfunction "CCPC_3") (pintype "bidirectional"))
    )
    (net (code "77") (name "Net-(MOTOR_1-OUT1)") (class "Default")
      (node (ref "C24") (pin "1") (pinfunction "1_1") (pintype "passive"))
      (node (ref "MOTOR_1") (pin "8") (pinfunction "OUT1_8") (pintype "bidirectional"))
      (node (ref "RIGHT") (pin "1") (pinfunction "2_1") (pintype "passive"))
    )
    (net (code "78") (name "Net-(MOTOR_1-OUT2)") (class "Default")
      (node (ref "C24") (pin "2") (pinfunction "2_2") (pintype "passive"))
      (node (ref "MOTOR_1") (pin "10") (pinfunction "OUT2_10") (pintype "bidirectional"))
      (node (ref "RIGHT") (pin "2") (pinfunction "1_2") (pintype "passive"))
    )
    (net (code "79") (name "Net-(MOTOR_1-VREG)") (class "Default")
      (node (ref "C27") (pin "1") (pinfunction "1_1") (pintype "passive"))
      (node (ref "MOTOR_1") (pin "15") (pinfunction "VREG_15") (pintype "bidirectional"))
    )
    (net (code "80") (name "Net-(MOTOR_2-CCPA)") (class "Default")
      (node (ref "C31") (pin "1") (pinfunction "1_1") (pintype "passive"))
      (node (ref "MOTOR_2") (pin "1") (pinfunction "CCPA_1") (pintype "bidirectional"))
    )
    (net (code "81") (name "Net-(MOTOR_2-CCPB)") (class "Default")
      (node (ref "C30") (pin "2") (pinfunction "2_2") (pintype "passive"))
      (node (ref "MOTOR_2") (pin "2") (pinfunction "CCPB_2") (pintype "bidirectional"))
    )
    (net (code "82") (name "Net-(MOTOR_2-CCPC)") (class "Default")
      (node (ref "C30") (pin "1") (pinfunction "1_1") (pintype "passive"))
      (node (ref "MOTOR_2") (pin "3") (pinfunction "CCPC_3") (pintype "bidirectional"))
    )
    (net (code "83") (name "Net-(MOTOR_2-VREG)") (class "Default")
      (node (ref "C32") (pin "1") (pinfunction "1_1") (pintype "passive"))
      (node (ref "MOTOR_2") (pin "15") (pinfunction "VREG_15") (pintype "bidirectional"))
    )
    (net (code "84") (name "Net-(MOTOR_3-CCPA)") (class "Default")
      (node (ref "C36") (pin "1") (pinfunction "1_1") (pintype "passive"))
      (node (ref "MOTOR_3") (pin "1") (pinfunction "CCPA_1") (pintype "bidirectional"))
    )
    (net (code "85") (name "Net-(MOTOR_3-CCPB)") (class "Default")
      (node (ref "C35") (pin "2") (pinfunction "2_2") (pintype "passive"))
      (node (ref "MOTOR_3") (pin "2") (pinfunction "CCPB_2") (pintype "bidirectional"))
    )
    (net (code "86") (name "Net-(MOTOR_3-CCPC)") (class "Default")
      (node (ref "C35") (pin "1") (pinfunction "1_1") (pintype "passive"))
      (node (ref "MOTOR_3") (pin "3") (pinfunction "CCPC_3") (pintype "bidirectional"))
    )
    (net (code "87") (name "Net-(MOTOR_3-VREG)") (class "Default")
      (node (ref "C48") (pin "1") (pinfunction "1_1") (pintype "passive"))
      (node (ref "MOTOR_3") (pin "15") (pinfunction "VREG_15") (pintype "bidirectional"))
    )
    (net (code "88") (name "Net-(MOTOR_4-CCPA)") (class "Default")
      (node (ref "C51") (pin "1") (pinfunction "1_1") (pintype "passive"))
      (node (ref "MOTOR_4") (pin "1") (pinfunction "CCPA_1") (pintype "bidirectional"))
    )
    (net (code "89") (name "Net-(MOTOR_4-CCPB)") (class "Default")
      (node (ref "C50") (pin "2") (pinfunction "2_2") (pintype "passive"))
      (node (ref "MOTOR_4") (pin "2") (pinfunction "CCPB_2") (pintype "bidirectional"))
    )
    (net (code "90") (name "Net-(MOTOR_4-CCPC)") (class "Default")
      (node (ref "C50") (pin "1") (pinfunction "1_1") (pintype "passive"))
      (node (ref "MOTOR_4") (pin "3") (pinfunction "CCPC_3") (pintype "bidirectional"))
    )
    (net (code "91") (name "Net-(MOTOR_4-VREG)") (class "Default")
      (node (ref "C55") (pin "1") (pinfunction "1_1") (pintype "passive"))
      (node (ref "MOTOR_4") (pin "15") (pinfunction "VREG_15") (pintype "bidirectional"))
    )
    (net (code "92") (name "Net-(MOTOR_FUSE-P2-Pad3)") (class "Default")
      (node (ref "MOTOR_FUSE") (pin "3") (pinfunction "P2_3") (pintype "bidirectional"))
      (node (ref "MOTOR_FUSE") (pin "4") (pinfunction "P2_4") (pintype "bidirectional"))
      (node (ref "MOTOR_SWITCH") (pin "1") (pinfunction "1_1") (pintype "passive"))
    )
    (net (code "93") (name "Net-(POWER-PadA)") (class "Default")
      (node (ref "POWER") (pin "A") (pinfunction "A_A") (pintype "passive"))
      (node (ref "R17") (pin "1") (pinfunction "1_1") (pintype "passive"))
    )
    (net (code "94") (name "Net-(VREG-3.3V-VI)") (class "Default")
      (node (ref "C13") (pin "1") (pinfunction "1_1") (pintype "passive"))
      (node (ref "D2") (pin "C") (pinfunction "C_C") (pintype "passive"))
      (node (ref "VREG-3.3V") (pin "3") (pinfunction "VI_3") (pintype "input"))
    )
    (net (code "95") (name "Net-(VREG-5V-VIN)") (class "Default")
      (node (ref "C11") (pin "1") (pinfunction "1_1") (pintype "passive"))
      (node (ref "LOGIC_SWITCH") (pin "1") (pinfunction "1_1") (pintype "passive"))
      (node (ref "VREG-5V") (pin "1") (pinfunction "VIN_1") (pintype "bidirectional"))
    )
    (net (code "96") (name "SCK") (class "Default")
      (node (ref "MASTER") (pin "14") (pinfunction "14/A0/PWM_14") (pintype "bidirectional"))
      (node (ref "PIXY_SPI") (pin "3") (pinfunction "3_3") (pintype "passive"))
      (node (ref "SLAVE_LIGHT") (pin "14") (pinfunction "14/A0/PWM_14") (pintype "bidirectional"))
      (node (ref "SLAVE_TSOP") (pin "14") (pinfunction "14/A0/PWM_14") (pintype "bidirectional"))
    )
    (net (code "97") (name "SCL") (class "Default")
      (node (ref "IMU") (pin "3") (pinfunction "3_3") (pintype "passive"))
      (node (ref "MASTER") (pin "19") (pinfunction "19/A5/SCL0_19") (pintype "bidirectional"))
      (node (ref "R1") (pin "1") (pinfunction "1_1") (pintype "passive"))
      (node (ref "R7") (pin "1") (pinfunction "1_1") (pintype "passive"))
      (node (ref "SCL") (pin "2") (pinfunction "S_2") (pintype "passive"))
      (node (ref "SLAVE_LIGHT") (pin "3") (pinfunction "3/PWM/CAN0TX/SCL2_3") (pintype "bidirectional"))
      (node (ref "SLAVE_TSOP") (pin "37") (pinfunction "37/A18/PWM/SCL1_37") (pintype "bidirectional"))
    )
    (net (code "98") (name "SCL_5V") (class "Default")
      (node (ref "PIXY_I2C") (pin "5") (pinfunction "5_5") (pintype "passive"))
      (node (ref "R8") (pin "1") (pinfunction "1_1") (pintype "passive"))
      (node (ref "SCL") (pin "3") (pinfunction "D_3") (pintype "passive"))
      (node (ref "SONAR") (pin "3") (pinfunction "3_3") (pintype "passive"))
    )
    (net (code "99") (name "SDA") (class "Default")
      (node (ref "IMU") (pin "4") (pinfunction "4_4") (pintype "passive"))
      (node (ref "MASTER") (pin "18") (pinfunction "18/A4/SDA0_18") (pintype "bidirectional"))
      (node (ref "R2") (pin "1") (pinfunction "1_1") (pintype "passive"))
      (node (ref "R5") (pin "1") (pinfunction "1_1") (pintype "passive"))
      (node (ref "SDA") (pin "2") (pinfunction "S_2") (pintype "passive"))
      (node (ref "SLAVE_LIGHT") (pin "4") (pinfunction "4/PWM/CAN0RX/SDA2_4") (pintype "bidirectional"))
      (node (ref "SLAVE_TSOP") (pin "38") (pinfunction "38/A19/PWM/SDA1_38") (pintype "bidirectional"))
    )
    (net (code "100") (name "SDA_5V") (class "Default")
      (node (ref "PIXY_I2C") (pin "9") (pinfunction "9_9") (pintype "passive"))
      (node (ref "R6") (pin "1") (pinfunction "1_1") (pintype "passive"))
      (node (ref "SDA") (pin "3") (pinfunction "D_3") (pintype "passive"))
      (node (ref "SONAR") (pin "2") (pinfunction "2_2") (pintype "passive"))
    )
    (net (code "101") (name "TSOP0") (class "Default")
      (node (ref "0") (pin "OUT") (pinfunction "OUT_OUT") (pintype "bidirectional"))
      (node (ref "SLAVE_TSOP") (pin "0") (pinfunction "0/RX1/MOSI1_0") (pintype "bidirectional"))
    )
    (net (code "102") (name "TSOP1") (class "Default")
      (node (ref "1") (pin "OUT") (pinfunction "OUT_OUT") (pintype "bidirectional"))
      (node (ref "SLAVE_TSOP") (pin "1") (pinfunction "1/TX1/MISO1_1") (pintype "bidirectional"))
    )
    (net (code "103") (name "TSOP2") (class "Default")
      (node (ref "2") (pin "OUT") (pinfunction "OUT_OUT") (pintype "bidirectional"))
      (node (ref "SLAVE_TSOP") (pin "2") (pinfunction "2/PWM_2") (pintype "bidirectional"))
    )
    (net (code "104") (name "TSOP3") (class "Default")
      (node (ref "3") (pin "OUT") (pinfunction "OUT_OUT") (pintype "bidirectional"))
      (node (ref "SLAVE_TSOP") (pin "3") (pinfunction "3/PWM/CAN0TX/SCL2_3") (pintype "bidirectional"))
    )
    (net (code "105") (name "TSOP4") (class "Default")
      (node (ref "4") (pin "OUT") (pinfunction "OUT_OUT") (pintype "bidirectional"))
      (node (ref "SLAVE_TSOP") (pin "4") (pinfunction "4/PWM/CAN0RX/SDA2_4") (pintype "bidirectional"))
    )
    (net (code "106") (name "TSOP5") (class "Default")
      (node (ref "5") (pin "OUT") (pinfunction "OUT_OUT") (pintype "bidirectional"))
      (node (ref "SLAVE_TSOP") (pin "5") (pinfunction "5/PWM_5") (pintype "bidirectional"))
    )
    (net (code "107") (name "TSOP6") (class "Default")
      (node (ref "6") (pin "OUT") (pinfunction "OUT_OUT") (pintype "bidirectional"))
      (node (ref "SLAVE_TSOP") (pin "6") (pinfunction "6/PWM_6") (pintype "bidirectional"))
    )
    (net (code "108") (name "TSOP7") (class "Default")
      (node (ref "7") (pin "OUT") (pinfunction "OUT_OUT") (pintype "bidirectional"))
      (node (ref "SLAVE_TSOP") (pin "7") (pinfunction "7/PWM/RX3_7") (pintype "bidirectional"))
    )
    (net (code "109") (name "TSOP8") (class "Default")
      (node (ref "8") (pin "OUT") (pinfunction "OUT_OUT") (pintype "bidirectional"))
      (node (ref "SLAVE_TSOP") (pin "8") (pinfunction "8/PWM/TX3_8") (pintype "bidirectional"))
    )
    (net (code "110") (name "TSOP9") (class "Default")
      (node (ref "9") (pin "OUT") (pinfunction "OUT_OUT") (pintype "bidirectional"))
      (node (ref "SLAVE_TSOP") (pin "9") (pinfunction "9/PWM/RX2/CS0_9") (pintype "bidirectional"))
    )
    (net (code "111") (name "TSOP10") (class "Default")
      (node (ref "10") (pin "OUT") (pinfunction "OUT_OUT") (pintype "bidirectional"))
      (node (ref "SLAVE_TSOP") (pin "15") (pinfunction "15/A1/CS0_15") (pintype "bidirectional"))
    )
    (net (code "112") (name "TSOP11") (class "Default")
      (node (ref "11") (pin "OUT") (pinfunction "OUT_OUT") (pintype "bidirectional"))
      (node (ref "SLAVE_TSOP") (pin "16") (pinfunction "16/A2_16") (pintype "bidirectional"))
    )
    (net (code "113") (name "TSOP12") (class "Default")
      (node (ref "12") (pin "OUT") (pinfunction "OUT_OUT") (pintype "bidirectional"))
      (node (ref "SLAVE_TSOP") (pin "17") (pinfunction "17/A3_17") (pintype "bidirectional"))
    )
    (net (code "114") (name "TSOP13") (class "Default")
      (node (ref "13") (pin "OUT") (pinfunction "OUT_OUT") (pintype "bidirectional"))
      (node (ref "SLAVE_TSOP") (pin "18") (pinfunction "18/A4/SDA0_18") (pintype "bidirectional"))
    )
    (net (code "115") (name "TSOP14") (class "Default")
      (node (ref "14") (pin "OUT") (pinfunction "OUT_OUT") (pintype "bidirectional"))
      (node (ref "SLAVE_TSOP") (pin "19") (pinfunction "19/A5/SCL0_19") (pintype "bidirectional"))
    )
    (net (code "116") (name "TSOP15") (class "Default")
      (node (ref "15") (pin "OUT") (pinfunction "OUT_OUT") (pintype "bidirectional"))
      (node (ref "SLAVE_TSOP") (pin "20") (pinfunction "20/A6/PWM/CS0_20") (pintype "bidirectional"))
    )
    (net (code "117") (name "TSOP16") (class "Default")
      (node (ref "16") (pin "OUT") (pinfunction "OUT_OUT") (pintype "bidirectional"))
      (node (ref "SLAVE_TSOP") (pin "21") (pinfunction "21/A7/PWM/CS0_21") (pintype "bidirectional"))
    )
    (net (code "118") (name "TSOP17") (class "Default")
      (node (ref "17") (pin "OUT") (pinfunction "OUT_OUT") (pintype "bidirectional"))
      (node (ref "SLAVE_TSOP") (pin "22") (pinfunction "22/A8/PWM_22") (pintype "bidirectional"))
    )
    (net (code "119") (name "TSOP18") (class "Default")
      (node (ref "18") (pin "OUT") (pinfunction "OUT_OUT") (pintype "bidirectional"))
      (node (ref "SLAVE_TSOP") (pin "23") (pinfunction "23/A9/PWM_23") (pintype "bidirectional"))
    )
    (net (code "120") (name "TSOP19") (class "Default")
      (node (ref "19") (pin "OUT") (pinfunction "OUT_OUT") (pintype "bidirectional"))
      (node (ref "SLAVE_TSOP") (pin "24") (pinfunction "24_24") (pintype "bidirectional"))
    )
    (net (code "121") (name "TSOP20") (class "Default")
      (node (ref "20") (pin "OUT") (pinfunction "OUT_OUT") (pintype "bidirectional"))
      (node (ref "SLAVE_TSOP") (pin "25") (pinfunction "25_25") (pintype "bidirectional"))
    )
    (net (code "122") (name "TSOP21") (class "Default")
      (node (ref "21") (pin "OUT") (pinfunction "OUT_OUT") (pintype "bidirectional"))
      (node (ref "SLAVE_TSOP") (pin "26") (pinfunction "26_26") (pintype "bidirectional"))
    )
    (net (code "123") (name "TSOP22") (class "Default")
      (node (ref "22") (pin "OUT") (pinfunction "OUT_OUT") (pintype "bidirectional"))
      (node (ref "SLAVE_TSOP") (pin "27") (pinfunction "27_27") (pintype "bidirectional"))
    )
    (net (code "124") (name "TSOP23") (class "Default")
      (node (ref "23") (pin "OUT") (pinfunction "OUT_OUT") (pintype "bidirectional"))
      (node (ref "SLAVE_TSOP") (pin "28") (pinfunction "28_28") (pintype "bidirectional"))
    )
    (net (code "125") (name "TSOP_PWR") (class "Default")
      (node (ref "0") (pin "V+") (pinfunction "V+_V+") (pintype "bidirectional"))
      (node (ref "1") (pin "V+") (pinfunction "V+_V+") (pintype "bidirectional"))
      (node (ref "10") (pin "V+") (pinfunction "V+_V+") (pintype "bidirectional"))
      (node (ref "11") (pin "V+") (pinfunction "V+_V+") (pintype "bidirectional"))
      (node (ref "12") (pin "V+") (pinfunction "V+_V+") (pintype "bidirectional"))
      (node (ref "13") (pin "V+") (pinfunction "V+_V+") (pintype "bidirectional"))
      (node (ref "14") (pin "V+") (pinfunction "V+_V+") (pintype "bidirectional"))
      (node (ref "15") (pin "V+") (pinfunction "V+_V+") (pintype "bidirectional"))
      (node (ref "16") (pin "V+") (pinfunction "V+_V+") (pintype "bidirectional"))
      (node (ref "17") (pin "V+") (pinfunction "V+_V+") (pintype "bidirectional"))
      (node (ref "18") (pin "V+") (pinfunction "V+_V+") (pintype "bidirectional"))
      (node (ref "19") (pin "V+") (pinfunction "V+_V+") (pintype "bidirectional"))
      (node (ref "2") (pin "V+") (pinfunction "V+_V+") (pintype "bidirectional"))
      (node (ref "20") (pin "V+") (pinfunction "V+_V+") (pintype "bidirectional"))
      (node (ref "21") (pin "V+") (pinfunction "V+_V+") (pintype "bidirectional"))
      (node (ref "22") (pin "V+") (pinfunction "V+_V+") (pintype "bidirectional"))
      (node (ref "23") (pin "V+") (pinfunction "V+_V+") (pintype "bidirectional"))
      (node (ref "3") (pin "V+") (pinfunction "V+_V+") (pintype "bidirectional"))
      (node (ref "4") (pin "V+") (pinfunction "V+_V+") (pintype "bidirectional"))
      (node (ref "5") (pin "V+") (pinfunction "V+_V+") (pintype "bidirectional"))
      (node (ref "6") (pin "V+") (pinfunction "V+_V+") (pintype "bidirectional"))
      (node (ref "7") (pin "V+") (pinfunction "V+_V+") (pintype "bidirectional"))
      (node (ref "8") (pin "V+") (pinfunction "V+_V+") (pintype "bidirectional"))
      (node (ref "9") (pin "V+") (pinfunction "V+_V+") (pintype "bidirectional"))
      (node (ref "C10") (pin "1") (pinfunction "1_1") (pintype "passive"))
      (node (ref "C16") (pin "1") (pinfunction "1_1") (pintype "passive"))
      (node (ref "C17") (pin "1") (pinfunction "1_1") (pintype "passive"))
      (node (ref "C18") (pin "1") (pinfunction "1_1") (pintype "passive"))
      (node (ref "C19") (pin "1") (pinfunction "1_1") (pintype "passive"))
      (node (ref "C20") (pin "1") (pinfunction "1_1") (pintype "passive"))
      (node (ref "C21") (pin "1") (pinfunction "1_1") (pintype "passive"))
      (node (ref "C22") (pin "1") (pinfunction "1_1") (pintype "passive"))
      (node (ref "C23") (pin "1") (pinfunction "1_1") (pintype "passive"))
      (node (ref "C3") (pin "1") (pinfunction "1_1") (pintype "passive"))
      (node (ref "C4") (pin "1") (pinfunction "1_1") (pintype "passive"))
      (node (ref "C40") (pin "1") (pinfunction "1_1") (pintype "passive"))
      (node (ref "C41") (pin "1") (pinfunction "1_1") (pintype "passive"))
      (node (ref "C42") (pin "1") (pinfunction "1_1") (pintype "passive"))
      (node (ref "C43") (pin "1") (pinfunction "1_1") (pintype "passive"))
      (node (ref "C44") (pin "1") (pinfunction "1_1") (pintype "passive"))
      (node (ref "C45") (pin "1") (pinfunction "1_1") (pintype "passive"))
      (node (ref "C46") (pin "1") (pinfunction "1_1") (pintype "passive"))
      (node (ref "C47") (pin "1") (pinfunction "1_1") (pintype "passive"))
      (node (ref "C5") (pin "1") (pinfunction "1_1") (pintype "passive"))
      (node (ref "C6") (pin "1") (pinfunction "1_1") (pintype "passive"))
      (node (ref "C7") (pin "1") (pinfunction "1_1") (pintype "passive"))
      (node (ref "C8") (pin "1") (pinfunction "1_1") (pintype "passive"))
      (node (ref "C9") (pin "1") (pinfunction "1_1") (pintype "passive"))
      (node (ref "SLAVE_TSOP") (pin "29") (pinfunction "29/PWM_29") (pintype "bidirectional"))
      (node (ref "SLAVE_TSOP") (pin "30") (pinfunction "30/PWM_30") (pintype "bidirectional"))
      (node (ref "SLAVE_TSOP") (pin "31") (pinfunction "31/A12/RX4/CS1_31") (pintype "bidirectional"))
      (node (ref "SLAVE_TSOP") (pin "32") (pinfunction "32/A13/TX4/SCK1_32") (pintype "bidirectional"))
    )
    (net (code "126") (name "unconnected-(BLUETOOTH-Pad1)") (class "Default")
      (node (ref "BLUETOOTH") (pin "1") (pinfunction "1_1") (pintype "passive"))
    )
    (net (code "127") (name "unconnected-(BLUETOOTH-Pad6)") (class "Default")
      (node (ref "BLUETOOTH") (pin "6") (pinfunction "6_6") (pintype "passive"))
    )
    (net (code "128") (name "unconnected-(IMU-Pad5)") (class "Default")
      (node (ref "IMU") (pin "5") (pinfunction "5_5") (pintype "passive"))
    )
    (net (code "129") (name "unconnected-(IMU-Pad6)") (class "Default")
      (node (ref "IMU") (pin "6") (pinfunction "6_6") (pintype "passive"))
    )
    (net (code "130") (name "unconnected-(IMU-Pad7)") (class "Default")
      (node (ref "IMU") (pin "7") (pinfunction "7_7") (pintype "passive"))
    )
    (net (code "131") (name "unconnected-(IMU-Pad8)") (class "Default")
      (node (ref "IMU") (pin "8") (pinfunction "8_8") (pintype "passive"))
    )
    (net (code "132") (name "unconnected-(IMU-Pad9)") (class "Default")
      (node (ref "IMU") (pin "9") (pinfunction "9_9") (pintype "passive"))
    )
    (net (code "133") (name "unconnected-(IMU-Pad10)") (class "Default")
      (node (ref "IMU") (pin "10") (pinfunction "10_10") (pintype "passive"))
    )
    (net (code "134") (name "unconnected-(MASTER-13{slash}SCK0-Pad13)") (class "Default")
      (node (ref "MASTER") (pin "13") (pinfunction "13/SCK0_13") (pintype "bidirectional"))
    )
    (net (code "135") (name "unconnected-(MASTER-31{slash}A12{slash}RX4{slash}CS1-Pad31)") (class "Default")
      (node (ref "MASTER") (pin "31") (pinfunction "31/A12/RX4/CS1_31") (pintype "bidirectional"))
    )
    (net (code "136") (name "unconnected-(MASTER-32{slash}A13{slash}TX4{slash}SCK1-Pad32)") (class "Default")
      (node (ref "MASTER") (pin "32") (pinfunction "32/A13/TX4/SCK1_32") (pintype "bidirectional"))
    )
    (net (code "137") (name "unconnected-(MASTER-43{slash}CS2-Pad43)") (class "Default")
      (node (ref "MASTER") (pin "43") (pinfunction "43/CS2_43") (pintype "bidirectional"))
    )
    (net (code "138") (name "unconnected-(MASTER-44{slash}MOSI2-Pad44)") (class "Default")
      (node (ref "MASTER") (pin "44") (pinfunction "44/MOSI2_44") (pintype "bidirectional"))
    )
    (net (code "139") (name "unconnected-(MASTER-45{slash}MISO2-Pad45)") (class "Default")
      (node (ref "MASTER") (pin "45") (pinfunction "45/MISO2_45") (pintype "bidirectional"))
    )
    (net (code "140") (name "unconnected-(MASTER-46{slash}SCK2-Pad46)") (class "Default")
      (node (ref "MASTER") (pin "46") (pinfunction "46/SCK2_46") (pintype "bidirectional"))
    )
    (net (code "141") (name "unconnected-(MASTER-47{slash}RX6-Pad47)") (class "Default")
      (node (ref "MASTER") (pin "47") (pinfunction "47/RX6_47") (pintype "bidirectional"))
    )
    (net (code "142") (name "unconnected-(MASTER-48{slash}TX6-Pad48)") (class "Default")
      (node (ref "MASTER") (pin "48") (pinfunction "48/TX6_48") (pintype "bidirectional"))
    )
    (net (code "143") (name "unconnected-(MASTER-49{slash}A23-Pad49)") (class "Default")
      (node (ref "MASTER") (pin "49") (pinfunction "49/A23_49") (pintype "bidirectional"))
    )
    (net (code "144") (name "unconnected-(MASTER-50{slash}A24-Pad50)") (class "Default")
      (node (ref "MASTER") (pin "50") (pinfunction "50/A24_50") (pintype "bidirectional"))
    )
    (net (code "145") (name "unconnected-(MASTER-54{slash}CS2-Pad54)") (class "Default")
      (node (ref "MASTER") (pin "54") (pinfunction "54/CS2_54") (pintype "bidirectional"))
    )
    (net (code "146") (name "unconnected-(MASTER-A21{slash}DAC0-PadDA0)") (class "Default")
      (node (ref "MASTER") (pin "DA0") (pinfunction "A21/DAC0_DA0") (pintype "bidirectional"))
    )
    (net (code "147") (name "unconnected-(MASTER-A22{slash}DAC1-PadDA1)") (class "Default")
      (node (ref "MASTER") (pin "DA1") (pinfunction "A22/DAC1_DA1") (pintype "bidirectional"))
    )
    (net (code "148") (name "unconnected-(MASTER-DEBUG-1-PadDD)") (class "Default")
      (node (ref "MASTER") (pin "DD") (pinfunction "DEBUG-1_DD") (pintype "bidirectional"))
    )
    (net (code "149") (name "unconnected-(MASTER-DEBUG-2-PadDE)") (class "Default")
      (node (ref "MASTER") (pin "DE") (pinfunction "DEBUG-2_DE") (pintype "bidirectional"))
    )
    (net (code "150") (name "unconnected-(MASTER-DEBUG-PadDC)") (class "Default")
      (node (ref "MASTER") (pin "DC") (pinfunction "DEBUG_DC") (pintype "bidirectional"))
    )
    (net (code "151") (name "unconnected-(MASTER-Pad3.3V-1)") (class "Default")
      (node (ref "MASTER") (pin "3.3V-1") (pinfunction "3.3V-1_3.3V-1") (pintype "bidirectional"))
    )
    (net (code "152") (name "unconnected-(MASTER-Pad3.3V-2)") (class "Default")
      (node (ref "MASTER") (pin "3.3V-2") (pinfunction "3.3V-2_3.3V-2") (pintype "bidirectional"))
    )
    (net (code "153") (name "unconnected-(MASTER-Pad3.3V-3)") (class "Default")
      (node (ref "MASTER") (pin "3.3V-3") (pinfunction "3.3V-3_3.3V-3") (pintype "bidirectional"))
    )
    (net (code "154") (name "unconnected-(MASTER-Pad25)") (class "Default")
      (node (ref "MASTER") (pin "25") (pinfunction "25_25") (pintype "bidirectional"))
    )
    (net (code "155") (name "unconnected-(MASTER-Pad26)") (class "Default")
      (node (ref "MASTER") (pin "26") (pinfunction "26_26") (pintype "bidirectional"))
    )
    (net (code "156") (name "unconnected-(MASTER-Pad27)") (class "Default")
      (node (ref "MASTER") (pin "27") (pinfunction "27_27") (pintype "bidirectional"))
    )
    (net (code "157") (name "unconnected-(MASTER-Pad28)") (class "Default")
      (node (ref "MASTER") (pin "28") (pinfunction "28_28") (pintype "bidirectional"))
    )
    (net (code "158") (name "unconnected-(MASTER-Pad40)") (class "Default")
      (node (ref "MASTER") (pin "40") (pinfunction "40_40") (pintype "bidirectional"))
    )
    (net (code "159") (name "unconnected-(MASTER-Pad41)") (class "Default")
      (node (ref "MASTER") (pin "41") (pinfunction "41_41") (pintype "bidirectional"))
    )
    (net (code "160") (name "unconnected-(MASTER-Pad42)") (class "Default")
      (node (ref "MASTER") (pin "42") (pinfunction "42_42") (pintype "bidirectional"))
    )
    (net (code "161") (name "unconnected-(MASTER-Pad51)") (class "Default")
      (node (ref "MASTER") (pin "51") (pinfunction "51_51") (pintype "bidirectional"))
    )
    (net (code "162") (name "unconnected-(MASTER-Pad52)") (class "Default")
      (node (ref "MASTER") (pin "52") (pinfunction "52_52") (pintype "bidirectional"))
    )
    (net (code "163") (name "unconnected-(MASTER-Pad53)") (class "Default")
      (node (ref "MASTER") (pin "53") (pinfunction "53_53") (pintype "bidirectional"))
    )
    (net (code "164") (name "unconnected-(MASTER-Pad55)") (class "Default")
      (node (ref "MASTER") (pin "55") (pinfunction "55_55") (pintype "bidirectional"))
    )
    (net (code "165") (name "unconnected-(MASTER-Pad56)") (class "Default")
      (node (ref "MASTER") (pin "56") (pinfunction "56_56") (pintype "bidirectional"))
    )
    (net (code "166") (name "unconnected-(MASTER-Pad57)") (class "Default")
      (node (ref "MASTER") (pin "57") (pinfunction "57_57") (pintype "bidirectional"))
    )
    (net (code "167") (name "unconnected-(MASTER-PadA10)") (class "Default")
      (node (ref "MASTER") (pin "A10") (pinfunction "A10_A10") (pintype "bidirectional"))
    )
    (net (code "168") (name "unconnected-(MASTER-PadA11)") (class "Default")
      (node (ref "MASTER") (pin "A11") (pinfunction "A11_A11") (pintype "bidirectional"))
    )
    (net (code "169") (name "unconnected-(MASTER-PadAREF)") (class "Default")
      (node (ref "MASTER") (pin "AREF") (pinfunction "AREF_AREF") (pintype "bidirectional"))
    )
    (net (code "170") (name "unconnected-(MASTER-PadPRGRM)") (class "Default")
      (node (ref "MASTER") (pin "PRGRM") (pinfunction "PRGRM_PRGRM") (pintype "bidirectional"))
    )
    (net (code "171") (name "unconnected-(MASTER-PadRESET)") (class "Default")
      (node (ref "MASTER") (pin "RESET") (pinfunction "RESET_RESET") (pintype "bidirectional"))
    )
    (net (code "172") (name "unconnected-(MASTER-PadVBAT)") (class "Default")
      (node (ref "MASTER") (pin "VBAT") (pinfunction "VBAT_VBAT") (pintype "bidirectional"))
    )
    (net (code "173") (name "unconnected-(MASTER-PadVIN)") (class "Default")
      (node (ref "MASTER") (pin "VIN") (pinfunction "VIN_VIN") (pintype "bidirectional"))
    )
    (net (code "174") (name "unconnected-(MASTER-PadVUSB)") (class "Default")
      (node (ref "MASTER") (pin "VUSB") (pinfunction "VUSB_VUSB") (pintype "bidirectional"))
    )
    (net (code "175") (name "unconnected-(PIXY_I2C-Pad1)") (class "Default")
      (node (ref "PIXY_I2C") (pin "1") (pinfunction "1_1") (pintype "passive"))
    )
    (net (code "176") (name "unconnected-(PIXY_I2C-Pad3)") (class "Default")
      (node (ref "PIXY_I2C") (pin "3") (pinfunction "3_3") (pintype "passive"))
    )
    (net (code "177") (name "unconnected-(PIXY_I2C-Pad4)") (class "Default")
      (node (ref "PIXY_I2C") (pin "4") (pinfunction "4_4") (pintype "passive"))
    )
    (net (code "178") (name "unconnected-(PIXY_I2C-Pad7)") (class "Default")
      (node (ref "PIXY_I2C") (pin "7") (pinfunction "7_7") (pintype "passive"))
    )
    (net (code "179") (name "unconnected-(PIXY_SPI-Pad5)") (class "Default")
      (node (ref "PIXY_SPI") (pin "5") (pinfunction "5_5") (pintype "passive"))
    )
    (net (code "180") (name "unconnected-(PIXY_SPI-Pad9)") (class "Default")
      (node (ref "PIXY_SPI") (pin "9") (pinfunction "9_9") (pintype "passive"))
    )
    (net (code "181") (name "unconnected-(SLAVE_LIGHT-0{slash}RX1{slash}MOSI1-Pad0)") (class "Default")
      (node (ref "SLAVE_LIGHT") (pin "0") (pinfunction "0/RX1/MOSI1_0") (pintype "bidirectional"))
    )
    (net (code "182") (name "unconnected-(SLAVE_LIGHT-1{slash}TX1{slash}MISO1-Pad1)") (class "Default")
      (node (ref "SLAVE_LIGHT") (pin "1") (pinfunction "1/TX1/MISO1_1") (pintype "bidirectional"))
    )
    (net (code "183") (name "unconnected-(SLAVE_LIGHT-2{slash}PWM-Pad2)") (class "Default")
      (node (ref "SLAVE_LIGHT") (pin "2") (pinfunction "2/PWM_2") (pintype "bidirectional"))
    )
    (net (code "184") (name "unconnected-(SLAVE_LIGHT-5{slash}PWM-Pad5)") (class "Default")
      (node (ref "SLAVE_LIGHT") (pin "5") (pinfunction "5/PWM_5") (pintype "bidirectional"))
    )
    (net (code "185") (name "unconnected-(SLAVE_LIGHT-6{slash}PWM-Pad6)") (class "Default")
      (node (ref "SLAVE_LIGHT") (pin "6") (pinfunction "6/PWM_6") (pintype "bidirectional"))
    )
    (net (code "186") (name "unconnected-(SLAVE_LIGHT-7{slash}PWM{slash}RX3-Pad7)") (class "Default")
      (node (ref "SLAVE_LIGHT") (pin "7") (pinfunction "7/PWM/RX3_7") (pintype "bidirectional"))
    )
    (net (code "187") (name "unconnected-(SLAVE_LIGHT-8{slash}PWM{slash}TX3-Pad8)") (class "Default")
      (node (ref "SLAVE_LIGHT") (pin "8") (pinfunction "8/PWM/TX3_8") (pintype "bidirectional"))
    )
    (net (code "188") (name "unconnected-(SLAVE_LIGHT-9{slash}PWM{slash}RX2{slash}CS0-Pad9)") (class "Default")
      (node (ref "SLAVE_LIGHT") (pin "9") (pinfunction "9/PWM/RX2/CS0_9") (pintype "bidirectional"))
    )
    (net (code "189") (name "unconnected-(SLAVE_LIGHT-13{slash}SCK0-Pad13)") (class "Default")
      (node (ref "SLAVE_LIGHT") (pin "13") (pinfunction "13/SCK0_13") (pintype "bidirectional"))
    )
    (net (code "190") (name "unconnected-(SLAVE_LIGHT-29{slash}PWM-Pad29)") (class "Default")
      (node (ref "SLAVE_LIGHT") (pin "29") (pinfunction "29/PWM_29") (pintype "bidirectional"))
    )
    (net (code "191") (name "unconnected-(SLAVE_LIGHT-30{slash}PWM-Pad30)") (class "Default")
      (node (ref "SLAVE_LIGHT") (pin "30") (pinfunction "30/PWM_30") (pintype "bidirectional"))
    )
    (net (code "192") (name "unconnected-(SLAVE_LIGHT-43{slash}CS2-Pad43)") (class "Default")
      (node (ref "SLAVE_LIGHT") (pin "43") (pinfunction "43/CS2_43") (pintype "bidirectional"))
    )
    (net (code "193") (name "unconnected-(SLAVE_LIGHT-44{slash}MOSI2-Pad44)") (class "Default")
      (node (ref "SLAVE_LIGHT") (pin "44") (pinfunction "44/MOSI2_44") (pintype "bidirectional"))
    )
    (net (code "194") (name "unconnected-(SLAVE_LIGHT-45{slash}MISO2-Pad45)") (class "Default")
      (node (ref "SLAVE_LIGHT") (pin "45") (pinfunction "45/MISO2_45") (pintype "bidirectional"))
    )
    (net (code "195") (name "unconnected-(SLAVE_LIGHT-46{slash}SCK2-Pad46)") (class "Default")
      (node (ref "SLAVE_LIGHT") (pin "46") (pinfunction "46/SCK2_46") (pintype "bidirectional"))
    )
    (net (code "196") (name "unconnected-(SLAVE_LIGHT-47{slash}RX6-Pad47)") (class "Default")
      (node (ref "SLAVE_LIGHT") (pin "47") (pinfunction "47/RX6_47") (pintype "bidirectional"))
    )
    (net (code "197") (name "unconnected-(SLAVE_LIGHT-48{slash}TX6-Pad48)") (class "Default")
      (node (ref "SLAVE_LIGHT") (pin "48") (pinfunction "48/TX6_48") (pintype "bidirectional"))
    )
    (net (code "198") (name "unconnected-(SLAVE_LIGHT-54{slash}CS2-Pad54)") (class "Default")
      (node (ref "SLAVE_LIGHT") (pin "54") (pinfunction "54/CS2_54") (pintype "bidirectional"))
    )
    (net (code "199") (name "unconnected-(SLAVE_LIGHT-DEBUG-1-PadDD)") (class "Default")
      (node (ref "SLAVE_LIGHT") (pin "DD") (pinfunction "DEBUG-1_DD") (pintype "bidirectional"))
    )
    (net (code "200") (name "unconnected-(SLAVE_LIGHT-DEBUG-2-PadDE)") (class "Default")
      (node (ref "SLAVE_LIGHT") (pin "DE") (pinfunction "DEBUG-2_DE") (pintype "bidirectional"))
    )
    (net (code "201") (name "unconnected-(SLAVE_LIGHT-DEBUG-PadDC)") (class "Default")
      (node (ref "SLAVE_LIGHT") (pin "DC") (pinfunction "DEBUG_DC") (pintype "bidirectional"))
    )
    (net (code "202") (name "unconnected-(SLAVE_LIGHT-Pad3.3V-1)") (class "Default")
      (node (ref "SLAVE_LIGHT") (pin "3.3V-1") (pinfunction "3.3V-1_3.3V-1") (pintype "bidirectional"))
    )
    (net (code "203") (name "unconnected-(SLAVE_LIGHT-Pad3.3V-2)") (class "Default")
      (node (ref "SLAVE_LIGHT") (pin "3.3V-2") (pinfunction "3.3V-2_3.3V-2") (pintype "bidirectional"))
    )
    (net (code "204") (name "unconnected-(SLAVE_LIGHT-Pad3.3V-3)") (class "Default")
      (node (ref "SLAVE_LIGHT") (pin "3.3V-3") (pinfunction "3.3V-3_3.3V-3") (pintype "bidirectional"))
    )
    (net (code "205") (name "unconnected-(SLAVE_LIGHT-Pad24)") (class "Default")
      (node (ref "SLAVE_LIGHT") (pin "24") (pinfunction "24_24") (pintype "bidirectional"))
    )
    (net (code "206") (name "unconnected-(SLAVE_LIGHT-Pad25)") (class "Default")
      (node (ref "SLAVE_LIGHT") (pin "25") (pinfunction "25_25") (pintype "bidirectional"))
    )
    (net (code "207") (name "unconnected-(SLAVE_LIGHT-Pad26)") (class "Default")
      (node (ref "SLAVE_LIGHT") (pin "26") (pinfunction "26_26") (pintype "bidirectional"))
    )
    (net (code "208") (name "unconnected-(SLAVE_LIGHT-Pad27)") (class "Default")
      (node (ref "SLAVE_LIGHT") (pin "27") (pinfunction "27_27") (pintype "bidirectional"))
    )
    (net (code "209") (name "unconnected-(SLAVE_LIGHT-Pad28)") (class "Default")
      (node (ref "SLAVE_LIGHT") (pin "28") (pinfunction "28_28") (pintype "bidirectional"))
    )
    (net (code "210") (name "unconnected-(SLAVE_LIGHT-Pad40)") (class "Default")
      (node (ref "SLAVE_LIGHT") (pin "40") (pinfunction "40_40") (pintype "bidirectional"))
    )
    (net (code "211") (name "unconnected-(SLAVE_LIGHT-Pad41)") (class "Default")
      (node (ref "SLAVE_LIGHT") (pin "41") (pinfunction "41_41") (pintype "bidirectional"))
    )
    (net (code "212") (name "unconnected-(SLAVE_LIGHT-Pad42)") (class "Default")
      (node (ref "SLAVE_LIGHT") (pin "42") (pinfunction "42_42") (pintype "bidirectional"))
    )
    (net (code "213") (name "unconnected-(SLAVE_LIGHT-Pad51)") (class "Default")
      (node (ref "SLAVE_LIGHT") (pin "51") (pinfunction "51_51") (pintype "bidirectional"))
    )
    (net (code "214") (name "unconnected-(SLAVE_LIGHT-Pad52)") (class "Default")
      (node (ref "SLAVE_LIGHT") (pin "52") (pinfunction "52_52") (pintype "bidirectional"))
    )
    (net (code "215") (name "unconnected-(SLAVE_LIGHT-Pad53)") (class "Default")
      (node (ref "SLAVE_LIGHT") (pin "53") (pinfunction "53_53") (pintype "bidirectional"))
    )
    (net (code "216") (name "unconnected-(SLAVE_LIGHT-Pad55)") (class "Default")
      (node (ref "SLAVE_LIGHT") (pin "55") (pinfunction "55_55") (pintype "bidirectional"))
    )
    (net (code "217") (name "unconnected-(SLAVE_LIGHT-Pad56)") (class "Default")
      (node (ref "SLAVE_LIGHT") (pin "56") (pinfunction "56_56") (pintype "bidirectional"))
    )
    (net (code "218") (name "unconnected-(SLAVE_LIGHT-Pad57)") (class "Default")
      (node (ref "SLAVE_LIGHT") (pin "57") (pinfunction "57_57") (pintype "bidirectional"))
    )
    (net (code "219") (name "unconnected-(SLAVE_LIGHT-PadAREF)") (class "Default")
      (node (ref "SLAVE_LIGHT") (pin "AREF") (pinfunction "AREF_AREF") (pintype "bidirectional"))
    )
    (net (code "220") (name "unconnected-(SLAVE_LIGHT-PadPRGRM)") (class "Default")
      (node (ref "SLAVE_LIGHT") (pin "PRGRM") (pinfunction "PRGRM_PRGRM") (pintype "bidirectional"))
    )
    (net (code "221") (name "unconnected-(SLAVE_LIGHT-PadRESET)") (class "Default")
      (node (ref "SLAVE_LIGHT") (pin "RESET") (pinfunction "RESET_RESET") (pintype "bidirectional"))
    )
    (net (code "222") (name "unconnected-(SLAVE_LIGHT-PadVBAT)") (class "Default")
      (node (ref "SLAVE_LIGHT") (pin "VBAT") (pinfunction "VBAT_VBAT") (pintype "bidirectional"))
    )
    (net (code "223") (name "unconnected-(SLAVE_LIGHT-PadVIN)") (class "Default")
      (node (ref "SLAVE_LIGHT") (pin "VIN") (pinfunction "VIN_VIN") (pintype "bidirectional"))
    )
    (net (code "224") (name "unconnected-(SLAVE_LIGHT-PadVUSB)") (class "Default")
      (node (ref "SLAVE_LIGHT") (pin "VUSB") (pinfunction "VUSB_VUSB") (pintype "bidirectional"))
    )
    (net (code "225") (name "unconnected-(SLAVE_TSOP-13{slash}SCK0-Pad13)") (class "Default")
      (node (ref "SLAVE_TSOP") (pin "13") (pinfunction "13/SCK0_13") (pintype "bidirectional"))
    )
    (net (code "226") (name "unconnected-(SLAVE_TSOP-33{slash}A14{slash}TX5-Pad33)") (class "Default")
      (node (ref "SLAVE_TSOP") (pin "33") (pinfunction "33/A14/TX5_33") (pintype "bidirectional"))
    )
    (net (code "227") (name "unconnected-(SLAVE_TSOP-34{slash}A15{slash}RX5-Pad34)") (class "Default")
      (node (ref "SLAVE_TSOP") (pin "34") (pinfunction "34/A15/RX5_34") (pintype "bidirectional"))
    )
    (net (code "228") (name "unconnected-(SLAVE_TSOP-35{slash}A16{slash}PWM-Pad35)") (class "Default")
      (node (ref "SLAVE_TSOP") (pin "35") (pinfunction "35/A16/PWM_35") (pintype "bidirectional"))
    )
    (net (code "229") (name "unconnected-(SLAVE_TSOP-36{slash}A17{slash}PWM-Pad36)") (class "Default")
      (node (ref "SLAVE_TSOP") (pin "36") (pinfunction "36/A17/PWM_36") (pintype "bidirectional"))
    )
    (net (code "230") (name "unconnected-(SLAVE_TSOP-39{slash}A20-Pad39)") (class "Default")
      (node (ref "SLAVE_TSOP") (pin "39") (pinfunction "39/A20_39") (pintype "bidirectional"))
    )
    (net (code "231") (name "unconnected-(SLAVE_TSOP-43{slash}CS2-Pad43)") (class "Default")
      (node (ref "SLAVE_TSOP") (pin "43") (pinfunction "43/CS2_43") (pintype "bidirectional"))
    )
    (net (code "232") (name "unconnected-(SLAVE_TSOP-44{slash}MOSI2-Pad44)") (class "Default")
      (node (ref "SLAVE_TSOP") (pin "44") (pinfunction "44/MOSI2_44") (pintype "bidirectional"))
    )
    (net (code "233") (name "unconnected-(SLAVE_TSOP-45{slash}MISO2-Pad45)") (class "Default")
      (node (ref "SLAVE_TSOP") (pin "45") (pinfunction "45/MISO2_45") (pintype "bidirectional"))
    )
    (net (code "234") (name "unconnected-(SLAVE_TSOP-46{slash}SCK2-Pad46)") (class "Default")
      (node (ref "SLAVE_TSOP") (pin "46") (pinfunction "46/SCK2_46") (pintype "bidirectional"))
    )
    (net (code "235") (name "unconnected-(SLAVE_TSOP-47{slash}RX6-Pad47)") (class "Default")
      (node (ref "SLAVE_TSOP") (pin "47") (pinfunction "47/RX6_47") (pintype "bidirectional"))
    )
    (net (code "236") (name "unconnected-(SLAVE_TSOP-48{slash}TX6-Pad48)") (class "Default")
      (node (ref "SLAVE_TSOP") (pin "48") (pinfunction "48/TX6_48") (pintype "bidirectional"))
    )
    (net (code "237") (name "unconnected-(SLAVE_TSOP-49{slash}A23-Pad49)") (class "Default")
      (node (ref "SLAVE_TSOP") (pin "49") (pinfunction "49/A23_49") (pintype "bidirectional"))
    )
    (net (code "238") (name "unconnected-(SLAVE_TSOP-50{slash}A24-Pad50)") (class "Default")
      (node (ref "SLAVE_TSOP") (pin "50") (pinfunction "50/A24_50") (pintype "bidirectional"))
    )
    (net (code "239") (name "unconnected-(SLAVE_TSOP-54{slash}CS2-Pad54)") (class "Default")
      (node (ref "SLAVE_TSOP") (pin "54") (pinfunction "54/CS2_54") (pintype "bidirectional"))
    )
    (net (code "240") (name "unconnected-(SLAVE_TSOP-A21{slash}DAC0-PadDA0)") (class "Default")
      (node (ref "SLAVE_TSOP") (pin "DA0") (pinfunction "A21/DAC0_DA0") (pintype "bidirectional"))
    )
    (net (code "241") (name "unconnected-(SLAVE_TSOP-A22{slash}DAC1-PadDA1)") (class "Default")
      (node (ref "SLAVE_TSOP") (pin "DA1") (pinfunction "A22/DAC1_DA1") (pintype "bidirectional"))
    )
    (net (code "242") (name "unconnected-(SLAVE_TSOP-DEBUG-1-PadDD)") (class "Default")
      (node (ref "SLAVE_TSOP") (pin "DD") (pinfunction "DEBUG-1_DD") (pintype "bidirectional"))
    )
    (net (code "243") (name "unconnected-(SLAVE_TSOP-DEBUG-2-PadDE)") (class "Default")
      (node (ref "SLAVE_TSOP") (pin "DE") (pinfunction "DEBUG-2_DE") (pintype "bidirectional"))
    )
    (net (code "244") (name "unconnected-(SLAVE_TSOP-DEBUG-PadDC)") (class "Default")
      (node (ref "SLAVE_TSOP") (pin "DC") (pinfunction "DEBUG_DC") (pintype "bidirectional"))
    )
    (net (code "245") (name "unconnected-(SLAVE_TSOP-Pad3.3V-1)") (class "Default")
      (node (ref "SLAVE_TSOP") (pin "3.3V-1") (pinfunction "3.3V-1_3.3V-1") (pintype "bidirectional"))
    )
    (net (code "246") (name "unconnected-(SLAVE_TSOP-Pad3.3V-2)") (class "Default")
      (node (ref "SLAVE_TSOP") (pin "3.3V-2") (pinfunction "3.3V-2_3.3V-2") (pintype "bidirectional"))
    )
    (net (code "247") (name "unconnected-(SLAVE_TSOP-Pad3.3V-3)") (class "Default")
      (node (ref "SLAVE_TSOP") (pin "3.3V-3") (pinfunction "3.3V-3_3.3V-3") (pintype "bidirectional"))
    )
    (net (code "248") (name "unconnected-(SLAVE_TSOP-Pad40)") (class "Default")
      (node (ref "SLAVE_TSOP") (pin "40") (pinfunction "40_40") (pintype "bidirectional"))
    )
    (net (code "249") (name "unconnected-(SLAVE_TSOP-Pad41)") (class "Default")
      (node (ref "SLAVE_TSOP") (pin "41") (pinfunction "41_41") (pintype "bidirectional"))
    )
    (net (code "250") (name "unconnected-(SLAVE_TSOP-Pad42)") (class "Default")
      (node (ref "SLAVE_TSOP") (pin "42") (pinfunction "42_42") (pintype "bidirectional"))
    )
    (net (code "251") (name "unconnected-(SLAVE_TSOP-Pad51)") (class "Default")
      (node (ref "SLAVE_TSOP") (pin "51") (pinfunction "51_51") (pintype "bidirectional"))
    )
    (net (code "252") (name "unconnected-(SLAVE_TSOP-Pad52)") (class "Default")
      (node (ref "SLAVE_TSOP") (pin "52") (pinfunction "52_52") (pintype "bidirectional"))
    )
    (net (code "253") (name "unconnected-(SLAVE_TSOP-Pad53)") (class "Default")
      (node (ref "SLAVE_TSOP") (pin "53") (pinfunction "53_53") (pintype "bidirectional"))
    )
    (net (code "254") (name "unconnected-(SLAVE_TSOP-Pad55)") (class "Default")
      (node (ref "SLAVE_TSOP") (pin "55") (pinfunction "55_55") (pintype "bidirectional"))
    )
    (net (code "255") (name "unconnected-(SLAVE_TSOP-Pad56)") (class "Default")
      (node (ref "SLAVE_TSOP") (pin "56") (pinfunction "56_56") (pintype "bidirectional"))
    )
    (net (code "256") (name "unconnected-(SLAVE_TSOP-Pad57)") (class "Default")
      (node (ref "SLAVE_TSOP") (pin "57") (pinfunction "57_57") (pintype "bidirectional"))
    )
    (net (code "257") (name "unconnected-(SLAVE_TSOP-PadA10)") (class "Default")
      (node (ref "SLAVE_TSOP") (pin "A10") (pinfunction "A10_A10") (pintype "bidirectional"))
    )
    (net (code "258") (name "unconnected-(SLAVE_TSOP-PadA11)") (class "Default")
      (node (ref "SLAVE_TSOP") (pin "A11") (pinfunction "A11_A11") (pintype "bidirectional"))
    )
    (net (code "259") (name "unconnected-(SLAVE_TSOP-PadAREF)") (class "Default")
      (node (ref "SLAVE_TSOP") (pin "AREF") (pinfunction "AREF_AREF") (pintype "bidirectional"))
    )
    (net (code "260") (name "unconnected-(SLAVE_TSOP-PadPRGRM)") (class "Default")
      (node (ref "SLAVE_TSOP") (pin "PRGRM") (pinfunction "PRGRM_PRGRM") (pintype "bidirectional"))
    )
    (net (code "261") (name "unconnected-(SLAVE_TSOP-PadRESET)") (class "Default")
      (node (ref "SLAVE_TSOP") (pin "RESET") (pinfunction "RESET_RESET") (pintype "bidirectional"))
    )
    (net (code "262") (name "unconnected-(SLAVE_TSOP-PadVBAT)") (class "Default")
      (node (ref "SLAVE_TSOP") (pin "VBAT") (pinfunction "VBAT_VBAT") (pintype "bidirectional"))
    )
    (net (code "263") (name "unconnected-(SLAVE_TSOP-PadVIN)") (class "Default")
      (node (ref "SLAVE_TSOP") (pin "VIN") (pinfunction "VIN_VIN") (pintype "bidirectional"))
    )
    (net (code "264") (name "unconnected-(SLAVE_TSOP-PadVUSB)") (class "Default")
      (node (ref "SLAVE_TSOP") (pin "VUSB") (pinfunction "VUSB_VUSB") (pintype "bidirectional"))
    )
  )
)
